# driver_sapog_compact.net
KiCad netlist of a schematic drawn in Altium Designer
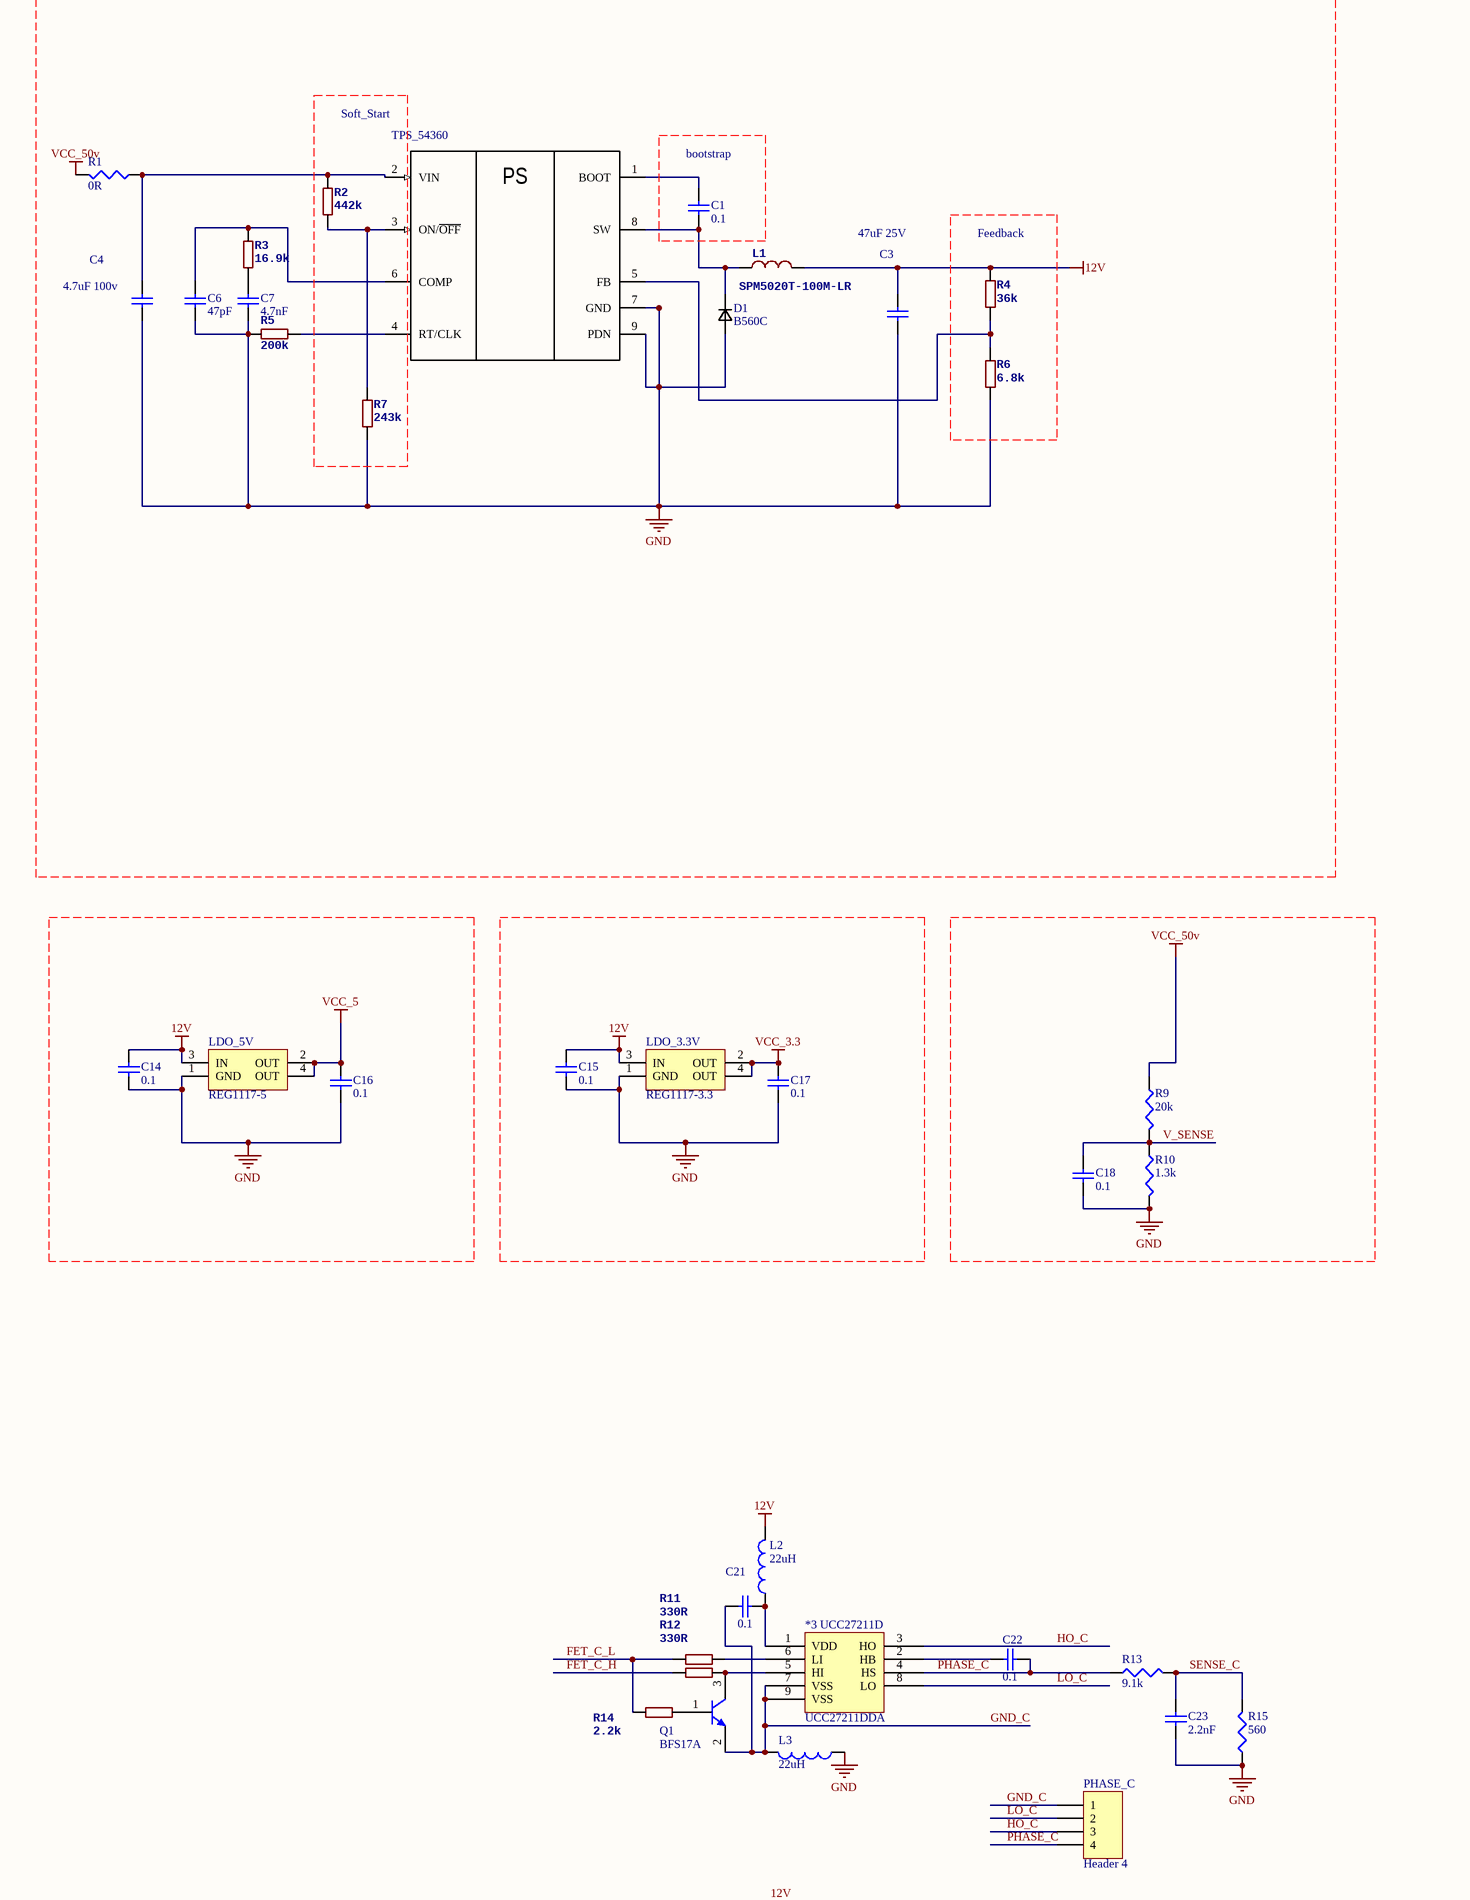
[diagram p0: driver_sapog_compact.SchDoc, top left]
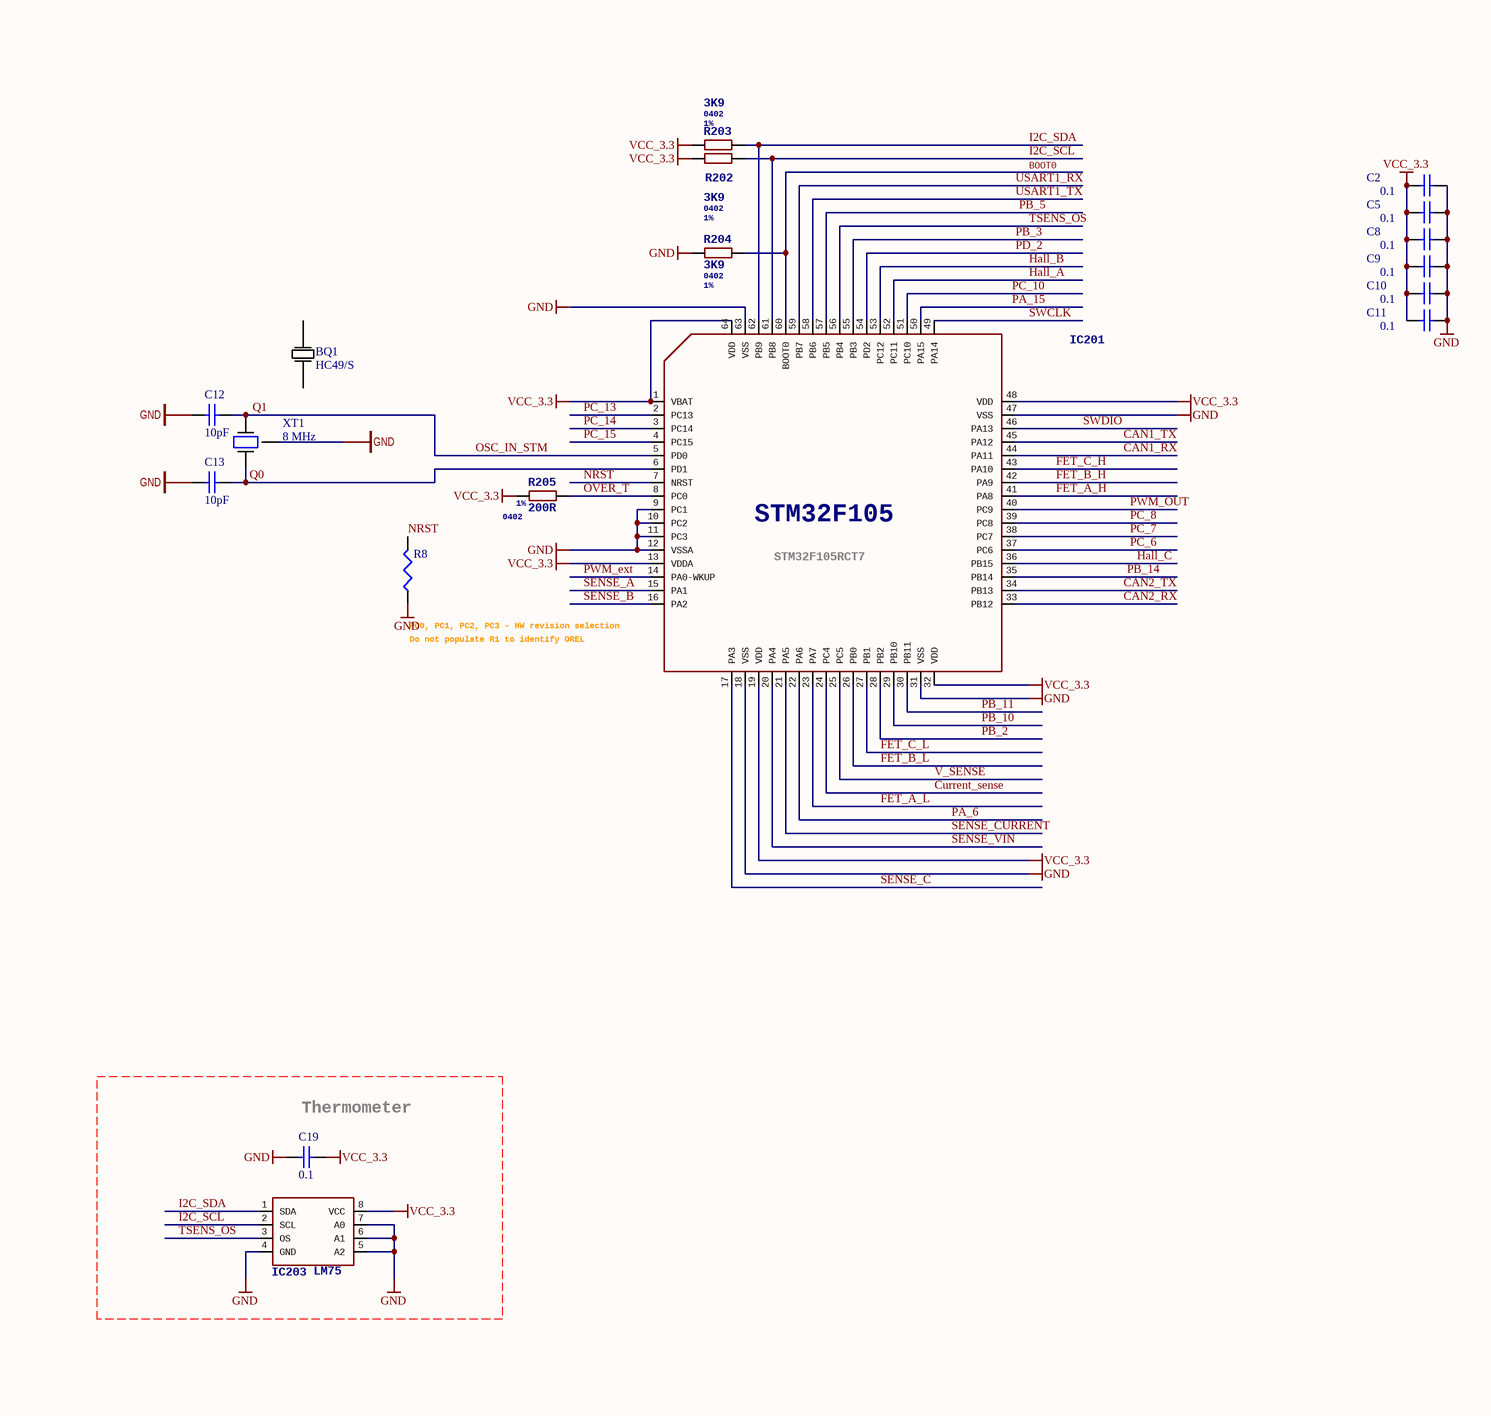
[diagram p1: driver_sapog_compact.SchDoc, top middle]
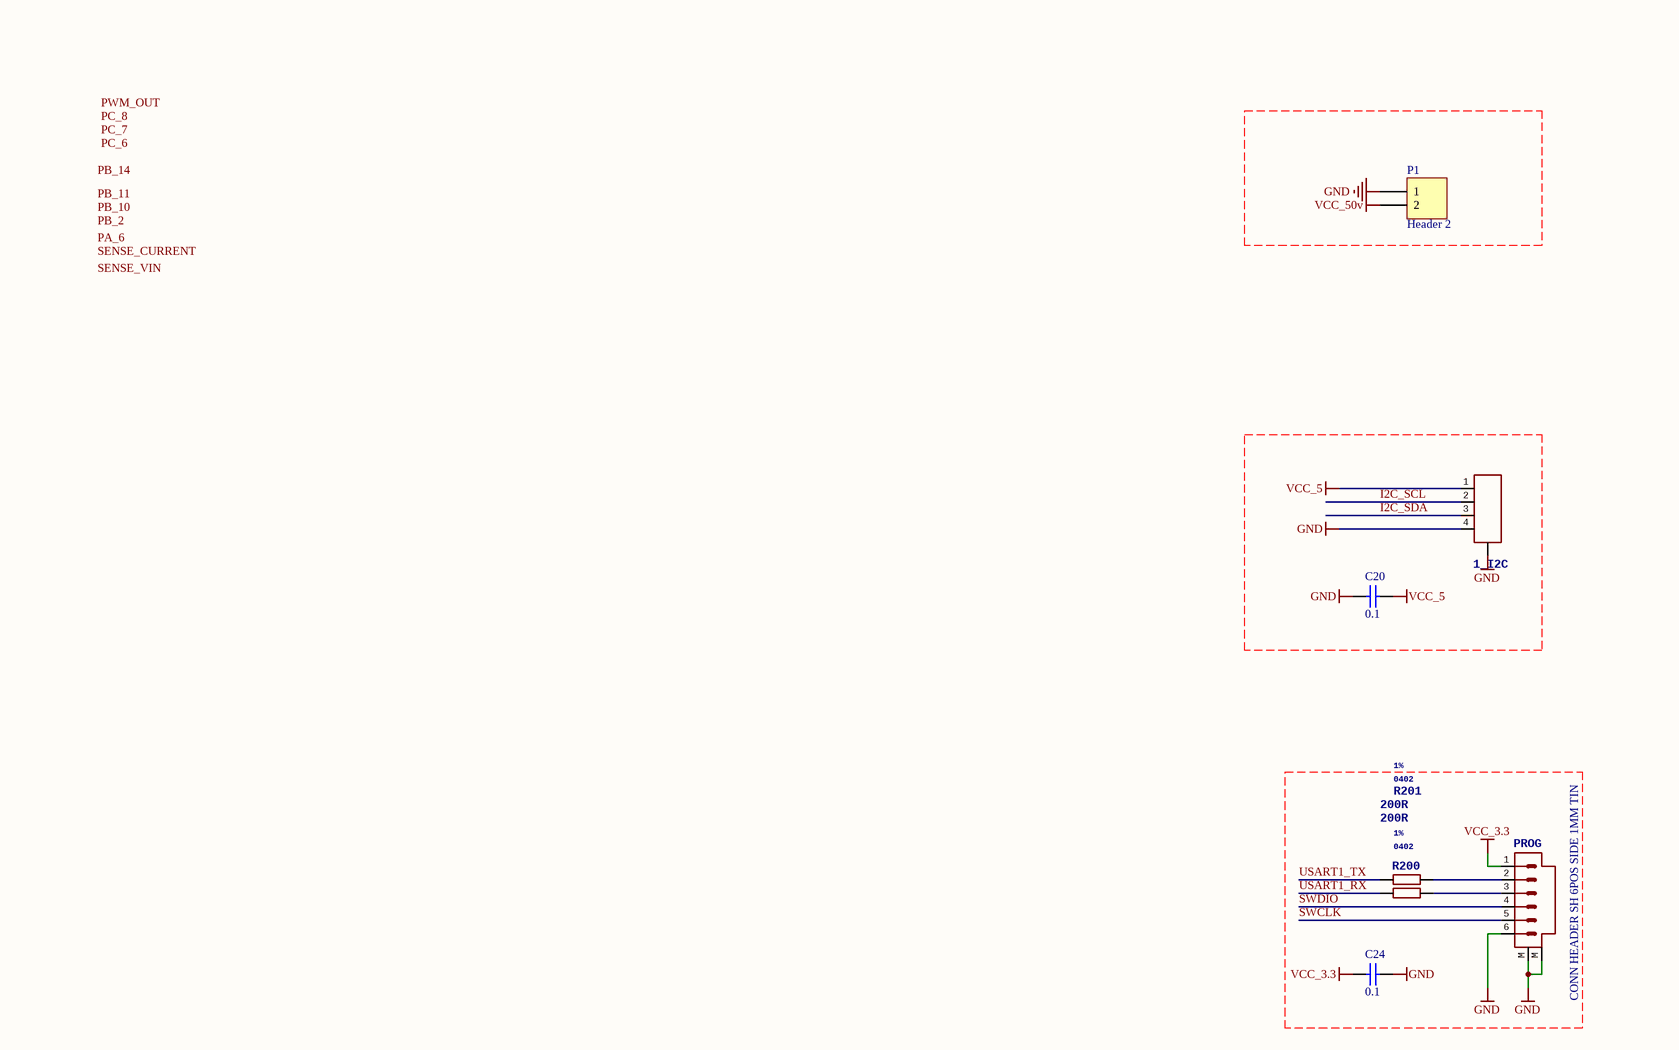
[diagram p2: driver_sapog_compact.SchDoc, top right]
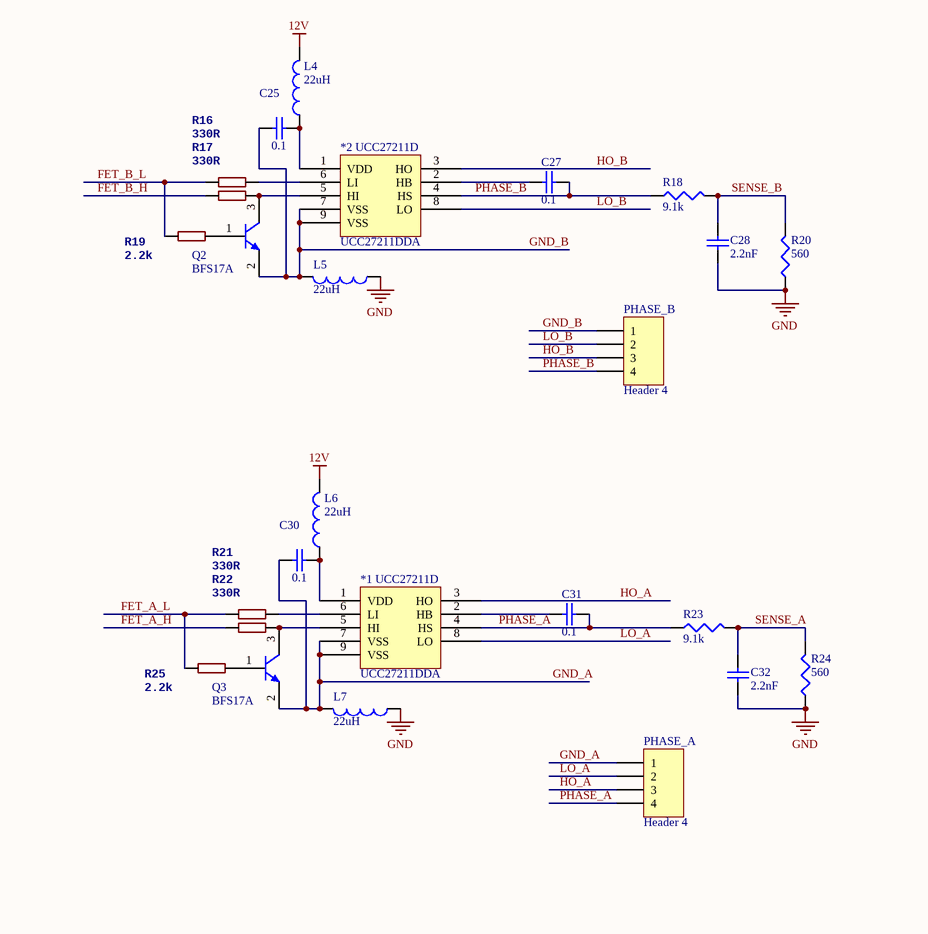
[diagram p3: driver_sapog_compact.SchDoc, bottom left]
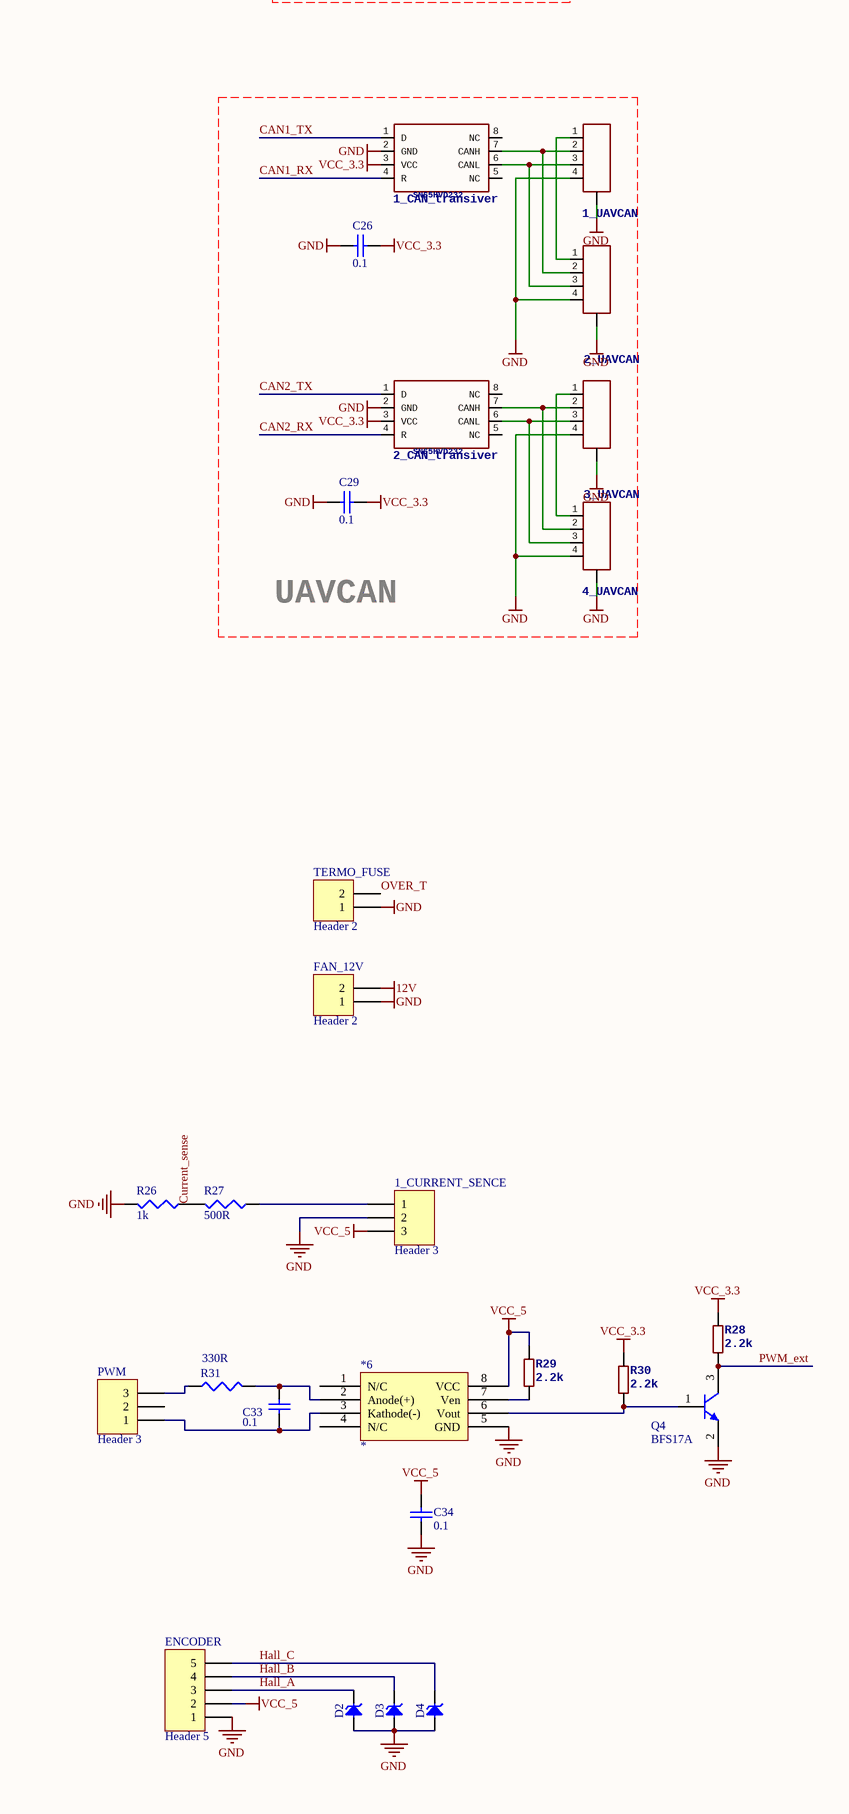
[diagram p4: driver_sapog_compact.SchDoc, bottom right]

(export (version "E")
  (design (tool "Eeschema 10.0.6"))
  (components
    (comp (ref "*1 UCC27211D")
      (value "UCC27211DDA")
      (footprint "Логическая_PLib:D8_L_G")
      (libsource (lib "UCC27211DDA") (part "UCC27211DDA"))
    )
    (comp (ref "*2 UCC27211D")
      (value "UCC27211DDA")
      (footprint "Логическая_PLib:D8_L_G")
      (libsource (lib "UCC27211DDA") (part "UCC27211DDA"))
    )
    (comp (ref "*3 UCC27211D")
      (value "UCC27211DDA")
      (footprint "Логическая_PLib:D8_L_G")
      (libsource (lib "UCC27211DDA") (part "UCC27211DDA"))
    )
    (comp (ref "*6") (value "*") (footprint "UCC37322P") (libsource (lib "HCPL0600") (part "Component_1")))
    (comp (ref "1_CAN_transiver")
      (value "SN65HVD232D")
      (footprint "SOIC8")
      (description "IC CAN TRANSCEIVER 3.3V 8-SOIC")
      (fields (field (name "MANF") "Texas Instruments") (field (name "SN65HVD232") "SN65HVD232"))
      (libsource (lib "sapog_reference_hardware") (part "SN65HVD232D"))
    )
    (comp (ref "1_CURRENT_SENCE")
      (value "Header 3")
      (footprint "HDR1X3")
      (description "Header, 3-Pin")
      (fields (field (name "PUBLISHER") "Altium Limited"))
      (libsource (lib "") (part "Header 3_1"))
    )
    (comp (ref "1_I2C")
      (value "CON-4P-RA")
      (footprint "JST_GH-4P-RA")
      (description "Connector Receptacle 4 Position 0.049\" (1.25mm) Tin Surface Mount, Right Angle")
      (fields (field (name "MANF") "Molex"))
      (libsource (lib "sapog_reference_hardware") (part "CON-4P-RA"))
    )
    (comp (ref "1_UAVCAN")
      (value "CON-4P-RA")
      (footprint "JST_GH-4P-RA")
      (description "Connector Receptacle 4 Position 0.049\" (1.25mm) Tin Surface Mount, Right Angle")
      (fields (field (name "MANF") "Molex"))
      (libsource (lib "sapog_reference_hardware") (part "CON-4P-RA"))
    )
    (comp (ref "2_CAN_transiver")
      (value "SN65HVD232D")
      (footprint "SOIC8")
      (description "IC CAN TRANSCEIVER 3.3V 8-SOIC")
      (fields (field (name "MANF") "Texas Instruments") (field (name "SN65HVD232") "SN65HVD232"))
      (libsource (lib "sapog_reference_hardware") (part "SN65HVD232D"))
    )
    (comp (ref "2_UAVCAN")
      (value "CON-4P-RA")
      (footprint "JST_GH-4P-RA")
      (description "Connector Receptacle 4 Position 0.049\" (1.25mm) Tin Surface Mount, Right Angle")
      (fields (field (name "MANF") "Molex"))
      (libsource (lib "sapog_reference_hardware") (part "CON-4P-RA"))
    )
    (comp (ref "3_UAVCAN")
      (value "CON-4P-RA")
      (footprint "JST_GH-4P-RA")
      (description "Connector Receptacle 4 Position 0.049\" (1.25mm) Tin Surface Mount, Right Angle")
      (fields (field (name "MANF") "Molex"))
      (libsource (lib "sapog_reference_hardware") (part "CON-4P-RA"))
    )
    (comp (ref "4_UAVCAN")
      (value "CON-4P-RA")
      (footprint "JST_GH-4P-RA")
      (description "Connector Receptacle 4 Position 0.049\" (1.25mm) Tin Surface Mount, Right Angle")
      (fields (field (name "MANF") "Molex"))
      (libsource (lib "sapog_reference_hardware") (part "CON-4P-RA"))
    )
    (comp (ref "BQ1")
      (value "HC49/S")
      (footprint "HS49/S")
      (description "Crystal Oscillator")
      (libsource (lib "Логическая_Lib") (part "HC49/S"))
    )
    (comp (ref "C1")
      (value "0.1")
      (footprint "1608[0603]")
      (description "Capacitor (Semiconductor SIM Model)")
      (fields (field (name "PUBLISHER") "Altium Limited"))
      (libsource (lib "Miscellaneous Devices") (part "Cap Semi"))
    )
    (comp (ref "C2")
      (value "0.1")
      (footprint "SMT0603/VISHAY")
      (description "Capacitor (Semiconductor SIM Model)")
      (fields (field (name "PUBLISHER") "Altium Limited"))
      (libsource (lib "Miscellaneous Devices") (part "Cap Semi"))
    )
    (comp (ref "C3")
      (value "47uF 25V")
      (footprint "2220")
      (description "100uF")
      (fields (field (name "Comment") "1206") (field (name "PUBLISHER") "Altium Limited"))
      (libsource (lib "Miscellaneous Devices") (part "Cap Semi"))
    )
    (comp (ref "C4")
      (value "4.7uF 100v")
      (footprint "2220")
      (fields (field (name "Comment") "2220") (field (name "PUBLISHER") "Altium Limited"))
      (libsource (lib "Miscellaneous Devices") (part "Cap Semi"))
    )
    (comp (ref "C5")
      (value "0.1")
      (footprint "SMT0603/VISHAY")
      (description "Capacitor (Semiconductor SIM Model)")
      (fields (field (name "PUBLISHER") "Altium Limited"))
      (libsource (lib "Miscellaneous Devices") (part "Cap Semi"))
    )
    (comp (ref "C6")
      (value "47pF")
      (footprint "SMT0603/VISHAY")
      (description "Capacitor (Semiconductor SIM Model)")
      (fields (field (name "PUBLISHER") "Altium Limited"))
      (libsource (lib "Miscellaneous Devices") (part "Cap Semi"))
    )
    (comp (ref "C7")
      (value "4.7nF")
      (footprint "SMT0603/VISHAY")
      (description "Capacitor (Semiconductor SIM Model)")
      (fields (field (name "PUBLISHER") "Altium Limited"))
      (libsource (lib "Miscellaneous Devices") (part "Cap Semi"))
    )
    (comp (ref "C8")
      (value "0.1")
      (footprint "SMT0603/VISHAY")
      (description "Capacitor (Semiconductor SIM Model)")
      (fields (field (name "PUBLISHER") "Altium Limited"))
      (libsource (lib "Miscellaneous Devices") (part "Cap Semi"))
    )
    (comp (ref "C9")
      (value "0.1")
      (footprint "SMT0603/VISHAY")
      (description "Capacitor (Semiconductor SIM Model)")
      (fields (field (name "PUBLISHER") "Altium Limited"))
      (libsource (lib "Miscellaneous Devices") (part "Cap Semi"))
    )
    (comp (ref "C10")
      (value "0.1")
      (footprint "SMT0603/VISHAY")
      (description "Capacitor (Semiconductor SIM Model)")
      (fields (field (name "PUBLISHER") "Altium Limited"))
      (libsource (lib "Miscellaneous Devices") (part "Cap Semi"))
    )
    (comp (ref "C11")
      (value "0.1")
      (footprint "SMT0603/VISHAY")
      (description "Capacitor (Semiconductor SIM Model)")
      (fields (field (name "PUBLISHER") "Altium Limited"))
      (libsource (lib "Miscellaneous Devices") (part "Cap Semi"))
    )
    (comp (ref "C12")
      (value "10pF")
      (footprint "SMT0603/VISHAY")
      (description "Capacitor (Semiconductor SIM Model)")
      (fields (field (name "PUBLISHER") "Altium Limited"))
      (libsource (lib "Miscellaneous Devices") (part "Cap Semi"))
    )
    (comp (ref "C13")
      (value "10pF")
      (footprint "SMT0603/VISHAY")
      (description "Capacitor (Semiconductor SIM Model)")
      (fields (field (name "PUBLISHER") "Altium Limited"))
      (libsource (lib "Miscellaneous Devices") (part "Cap Semi"))
    )
    (comp (ref "C14")
      (value "0.1")
      (footprint "SMT0603/VISHAY")
      (description "Capacitor (Semiconductor SIM Model)")
      (fields (field (name "PUBLISHER") "Altium Limited"))
      (libsource (lib "Miscellaneous Devices") (part "Cap Semi"))
    )
    (comp (ref "C15")
      (value "0.1")
      (footprint "SMT0603/VISHAY")
      (description "Capacitor (Semiconductor SIM Model)")
      (fields (field (name "PUBLISHER") "Altium Limited"))
      (libsource (lib "Miscellaneous Devices") (part "Cap Semi"))
    )
    (comp (ref "C16")
      (value "0.1")
      (footprint "SMT0603/VISHAY")
      (description "Capacitor (Semiconductor SIM Model)")
      (fields (field (name "PUBLISHER") "Altium Limited"))
      (libsource (lib "Miscellaneous Devices") (part "Cap Semi"))
    )
    (comp (ref "C17")
      (value "0.1")
      (footprint "SMT0603/VISHAY")
      (description "Capacitor (Semiconductor SIM Model)")
      (fields (field (name "PUBLISHER") "Altium Limited"))
      (libsource (lib "Miscellaneous Devices") (part "Cap Semi"))
    )
    (comp (ref "C18")
      (value "0.1")
      (footprint "SMT0603/VISHAY")
      (description "Capacitor (Semiconductor SIM Model)")
      (fields (field (name "PUBLISHER") "Altium Limited"))
      (libsource (lib "Miscellaneous Devices") (part "Cap Semi"))
    )
    (comp (ref "C19")
      (value "0.1")
      (footprint "SMT0603/VISHAY")
      (description "Capacitor (Semiconductor SIM Model)")
      (fields (field (name "PUBLISHER") "Altium Limited"))
      (libsource (lib "Miscellaneous Devices") (part "Cap Semi"))
    )
    (comp (ref "C20")
      (value "0.1")
      (footprint "SMT0603/VISHAY")
      (description "Capacitor (Semiconductor SIM Model)")
      (fields (field (name "PUBLISHER") "Altium Limited"))
      (libsource (lib "Miscellaneous Devices") (part "Cap Semi"))
    )
    (comp (ref "C21")
      (value "0.1")
      (footprint "2220")
      (description "Capacitor (Semiconductor SIM Model)")
      (fields (field (name "PUBLISHER") "Altium Limited"))
      (libsource (lib "Miscellaneous Devices") (part "Cap Semi"))
    )
    (comp (ref "C22")
      (value "0.1")
      (footprint "2220")
      (description "Capacitor (Semiconductor SIM Model)")
      (fields (field (name "PUBLISHER") "Altium Limited"))
      (libsource (lib "Miscellaneous Devices") (part "Cap Semi"))
    )
    (comp (ref "C23")
      (value "2.2nF")
      (footprint "SMT0603/VISHAY")
      (description "Capacitor (Semiconductor SIM Model)")
      (fields (field (name "PUBLISHER") "Altium Limited"))
      (libsource (lib "Miscellaneous Devices") (part "Cap Semi"))
    )
    (comp (ref "C24")
      (value "0.1")
      (footprint "SMT0603/VISHAY")
      (description "Capacitor (Semiconductor SIM Model)")
      (fields (field (name "PUBLISHER") "Altium Limited"))
      (libsource (lib "Miscellaneous Devices") (part "Cap Semi"))
    )
    (comp (ref "C25")
      (value "0.1")
      (footprint "2220")
      (description "Capacitor (Semiconductor SIM Model)")
      (fields (field (name "PUBLISHER") "Altium Limited"))
      (libsource (lib "Miscellaneous Devices") (part "Cap Semi"))
    )
    (comp (ref "C26")
      (value "0.1")
      (footprint "SMT0603/VISHAY")
      (description "Capacitor (Semiconductor SIM Model)")
      (fields (field (name "PUBLISHER") "Altium Limited"))
      (libsource (lib "Miscellaneous Devices") (part "Cap Semi"))
    )
    (comp (ref "C27")
      (value "0.1")
      (footprint "2220")
      (description "Capacitor (Semiconductor SIM Model)")
      (fields (field (name "PUBLISHER") "Altium Limited"))
      (libsource (lib "Miscellaneous Devices") (part "Cap Semi"))
    )
    (comp (ref "C28")
      (value "2.2nF")
      (footprint "SMT0603/VISHAY")
      (description "Capacitor (Semiconductor SIM Model)")
      (fields (field (name "PUBLISHER") "Altium Limited"))
      (libsource (lib "Miscellaneous Devices") (part "Cap Semi"))
    )
    (comp (ref "C29")
      (value "0.1")
      (footprint "SMT0603/VISHAY")
      (description "Capacitor (Semiconductor SIM Model)")
      (fields (field (name "PUBLISHER") "Altium Limited"))
      (libsource (lib "Miscellaneous Devices") (part "Cap Semi"))
    )
    (comp (ref "C30")
      (value "0.1")
      (footprint "2220")
      (description "Capacitor (Semiconductor SIM Model)")
      (fields (field (name "PUBLISHER") "Altium Limited"))
      (libsource (lib "Miscellaneous Devices") (part "Cap Semi"))
    )
    (comp (ref "C31")
      (value "0.1")
      (footprint "2220")
      (description "Capacitor (Semiconductor SIM Model)")
      (fields (field (name "PUBLISHER") "Altium Limited"))
      (libsource (lib "Miscellaneous Devices") (part "Cap Semi"))
    )
    (comp (ref "C32")
      (value "2.2nF")
      (footprint "SMT0603/VISHAY")
      (description "Capacitor (Semiconductor SIM Model)")
      (fields (field (name "PUBLISHER") "Altium Limited"))
      (libsource (lib "Miscellaneous Devices") (part "Cap Semi"))
    )
    (comp (ref "C33")
      (value "0.1")
      (footprint "SMT0603/VISHAY")
      (description "Capacitor (Semiconductor SIM Model)")
      (fields (field (name "PUBLISHER") "Altium Limited"))
      (libsource (lib "Miscellaneous Devices") (part "Cap Semi"))
    )
    (comp (ref "C34")
      (value "0.1")
      (footprint "SMT0603/VISHAY")
      (description "Capacitor (Semiconductor SIM Model)")
      (fields (field (name "PUBLISHER") "Altium Limited"))
      (libsource (lib "Miscellaneous Devices") (part "Cap Semi"))
    )
    (comp (ref "D1")
      (value "B560C")
      (footprint "SMC")
      (description "60V 0.5A Shottcky Diode")
      (libsource (lib "Логическая_Lib") (part "B560C"))
    )
    (comp (ref "D2")
      (value "BZV55-B13")
      (footprint "3.2x1.6x1.1")
      (description "Zener Diode")
      (fields
        (field (name "VOLTAGE") "13V")
        (field (name "POWER") "500mW")
        (field (name "AUTHOR") "CERN DEM JLC")
      )
      (libsource (lib "ICs And Semiconductors") (part "Diode Zener"))
    )
    (comp (ref "D3")
      (value "BZV55-B13")
      (footprint "3.2x1.6x1.1")
      (description "Zener Diode")
      (fields
        (field (name "VOLTAGE") "13V")
        (field (name "POWER") "500mW")
        (field (name "AUTHOR") "CERN DEM JLC")
      )
      (libsource (lib "ICs And Semiconductors") (part "Diode Zener"))
    )
    (comp (ref "D4")
      (value "BZV55-B13")
      (footprint "3.2x1.6x1.1")
      (description "Zener Diode")
      (fields
        (field (name "VOLTAGE") "13V")
        (field (name "POWER") "500mW")
        (field (name "AUTHOR") "CERN DEM JLC")
      )
      (libsource (lib "ICs And Semiconductors") (part "Diode Zener"))
    )
    (comp (ref "ENCODER")
      (value "Header 5")
      (footprint "jst_gh_6_pin")
      (description "Header, 5-Pin")
      (fields (field (name "PUBLISHER") "Altium Limited"))
      (libsource (lib "Miscellaneous Connectors") (part "Header 5"))
    )
    (comp (ref "FAN_12V")
      (value "Header 2")
      (footprint "HDR1X2")
      (description "Header, 2-Pin")
      (fields (field (name "PUBLISHER") "Altium Limited"))
      (libsource (lib "Miscellaneous Connectors") (part "Header 2"))
    )
    (comp (ref "IC201")
      (value "STM32F105")
      (footprint "sapog_reference_hardware:TQFP64-10X10")
      (description "MCU ARM 256KB FLASH MEM 64-LQFP")
      (fields (field (name "MANF") "STMicroelectronics") (field (name "STM32F105") "STM32F105"))
      (libsource (lib "sapog_reference_hardware") (part "STM32F105"))
    )
    (comp (ref "IC203")
      (value "LM75BD-TSSOP8")
      (footprint "TSSOP8")
      (description "SENSOR TEMPERATURE I2C 8TSSOP")
      (fields (field (name "MANF") "NXP Semiconductors") (field (name "LM75") "LM75"))
      (libsource (lib "sapog_reference_hardware") (part "LM75BD-TSSOP8"))
    )
    (comp (ref "L1")
      (value "SPM5020T-100M-LR")
      (footprint "RBQ:Inductor")
      (libsource (lib "sapog_reference_hardware") (part "L-EPCOS_B82464"))
    )
    (comp (ref "L2")
      (value "22uH")
      (footprint "0805")
      (description "0805")
      (fields (field (name "PUBLISHER") "Altium Limited"))
      (libsource (lib "Miscellaneous Devices") (part "Inductor"))
    )
    (comp (ref "L3")
      (value "22uH")
      (footprint "0805")
      (description "0805")
      (fields (field (name "PUBLISHER") "Altium Limited"))
      (libsource (lib "Miscellaneous Devices") (part "Inductor"))
    )
    (comp (ref "L4")
      (value "22uH")
      (footprint "0805")
      (description "0805")
      (fields (field (name "PUBLISHER") "Altium Limited"))
      (libsource (lib "Miscellaneous Devices") (part "Inductor"))
    )
    (comp (ref "L5")
      (value "22uH")
      (footprint "0805")
      (description "0805")
      (fields (field (name "PUBLISHER") "Altium Limited"))
      (libsource (lib "Miscellaneous Devices") (part "Inductor"))
    )
    (comp (ref "L6")
      (value "22uH")
      (footprint "0805")
      (description "0805")
      (fields (field (name "PUBLISHER") "Altium Limited"))
      (libsource (lib "Miscellaneous Devices") (part "Inductor"))
    )
    (comp (ref "L7")
      (value "22uH")
      (footprint "0805")
      (description "0805")
      (fields (field (name "PUBLISHER") "Altium Limited"))
      (libsource (lib "Miscellaneous Devices") (part "Inductor"))
    )
    (comp (ref "LDO_3.3V")
      (value "REG1117-3.3")
      (footprint "ZZ311")
      (description "800mA and 1A Low Dropout Positive Regulator 2.85V, 3.3V, 5V, and Adjustable")
      (fields (field (name "PUBLISHER") "Altium Limited"))
      (libsource (lib "BB Power Mgt Voltage Regulator") (part "REG1117-5"))
    )
    (comp (ref "LDO_5V")
      (value "REG1117-5")
      (footprint "ZZ311")
      (description "800mA and 1A Low Dropout Positive Regulator 2.85V, 3.3V, 5V, and Adjustable")
      (fields (field (name "PUBLISHER") "Altium Limited"))
      (libsource (lib "BB Power Mgt Voltage Regulator") (part "REG1117-5"))
    )
    (comp (ref "P1")
      (value "Header 2")
      (footprint "HDR1X2")
      (description "Header, 2-Pin")
      (fields (field (name "PUBLISHER") "Altium Limited"))
      (libsource (lib "") (part "Header 2_1"))
    )
    (comp (ref "PHASE_A")
      (value "Header 4")
      (footprint "HDR1X4")
      (description "Header, 4-Pin")
      (fields (field (name "PUBLISHER") "Altium Limited"))
      (libsource (lib "Miscellaneous Connectors") (part "Header 4"))
    )
    (comp (ref "PHASE_B")
      (value "Header 4")
      (footprint "HDR1X4")
      (description "Header, 4-Pin")
      (fields (field (name "PUBLISHER") "Altium Limited"))
      (libsource (lib "Miscellaneous Connectors") (part "Header 4"))
    )
    (comp (ref "PHASE_C")
      (value "Header 4")
      (footprint "HDR1X4")
      (description "Header, 4-Pin")
      (fields (field (name "PUBLISHER") "Altium Limited"))
      (libsource (lib "Miscellaneous Connectors") (part "Header 4"))
    )
    (comp (ref "PROG")
      (value "CONN HEADER SH 6POS SIDE 1MM TIN")
      (footprint "HIROSE DF13-6P-1.25H")
      (fields (field (name "MANF") "JST Sales America Inc"))
      (libsource (lib "sapog_reference_hardware") (part "DF13_6P_1"))
    )
    (comp (ref "PWM")
      (value "Header 3")
      (footprint "HDR1X3")
      (description "Header, 3-Pin")
      (fields (field (name "PUBLISHER") "Altium Limited"))
      (libsource (lib "Miscellaneous Connectors") (part "Header 3"))
    )
    (comp (ref "Q1")
      (value "BFS17A")
      (footprint "SOT-23_N")
      (description "NPN General Purpose Amplifier")
      (fields (field (name "PUBLISHER") "Altium Limited"))
      (libsource (lib "Miscellaneous Devices") (part "2N3904"))
    )
    (comp (ref "Q2")
      (value "BFS17A")
      (footprint "SOT-23_N")
      (description "NPN General Purpose Amplifier")
      (fields (field (name "PUBLISHER") "Altium Limited"))
      (libsource (lib "Miscellaneous Devices") (part "2N3904"))
    )
    (comp (ref "Q3")
      (value "BFS17A")
      (footprint "SOT-23_N")
      (description "NPN General Purpose Amplifier")
      (fields (field (name "PUBLISHER") "Altium Limited"))
      (libsource (lib "Miscellaneous Devices") (part "2N3904"))
    )
    (comp (ref "Q4")
      (value "BFS17A")
      (footprint "SOT-23_N")
      (description "NPN General Purpose Amplifier")
      (fields (field (name "PUBLISHER") "Altium Limited"))
      (libsource (lib "Miscellaneous Devices") (part "2N3904"))
    )
    (comp (ref "R1")
      (value "0R")
      (footprint "14-1210")
      (description "fuse")
      (fields (field (name "Comment") "1210") (field (name "PUBLISHER") "Altium Limited"))
      (libsource (lib "Miscellaneous Devices") (part "Res3"))
    )
    (comp (ref "R2")
      (value "442k")
      (footprint "SMT0603/VISHAY")
      (libsource (lib "sapog_reference_hardware") (part "R0402"))
    )
    (comp (ref "R3")
      (value "16.9k")
      (footprint "SMT0603/VISHAY")
      (libsource (lib "sapog_reference_hardware") (part "R0402"))
    )
    (comp (ref "R4")
      (value "36k")
      (footprint "SMT0603/VISHAY")
      (libsource (lib "sapog_reference_hardware") (part "R0402"))
    )
    (comp (ref "R5")
      (value "200k")
      (footprint "SMT0603/VISHAY")
      (libsource (lib "sapog_reference_hardware") (part "R0402"))
    )
    (comp (ref "R6")
      (value "6.8k")
      (footprint "SMT0603/VISHAY")
      (libsource (lib "sapog_reference_hardware") (part "R0402"))
    )
    (comp (ref "R7")
      (value "243k")
      (footprint "SMT0603/VISHAY")
      (libsource (lib "sapog_reference_hardware") (part "R0402"))
    )
    (comp (ref "R8")
      (value "Res3")
      (footprint "SMT0603/VISHAY")
      (description "Resistor")
      (fields (field (name "PUBLISHER") "Altium Limited"))
      (libsource (lib "Miscellaneous Devices") (part "Res3"))
    )
    (comp (ref "R9")
      (value "20k")
      (footprint "SMT0603/VISHAY")
      (description "Resistor")
      (fields (field (name "Comment") "10k") (field (name "PUBLISHER") "Altium Limited"))
      (libsource (lib "Miscellaneous Devices") (part "Res3"))
    )
    (comp (ref "R10")
      (value "1.3k")
      (footprint "SMT0603/VISHAY")
      (description "Resistor")
      (fields (field (name "Comment") "1k") (field (name "PUBLISHER") "Altium Limited"))
      (libsource (lib "Miscellaneous Devices") (part "Res3"))
    )
    (comp (ref "R11")
      (value "330R")
      (footprint "1608[0603]")
      (libsource (lib "sapog_reference_hardware") (part "R0402"))
    )
    (comp (ref "R12")
      (value "330R")
      (footprint "1608[0603]")
      (libsource (lib "sapog_reference_hardware") (part "R0402"))
    )
    (comp (ref "R13")
      (value "9.1k")
      (footprint "SMT0603/VISHAY")
      (description "Resistor")
      (fields (field (name "PUBLISHER") "Altium Limited"))
      (libsource (lib "Miscellaneous Devices") (part "Res3"))
    )
    (comp (ref "R14")
      (value "2.2k")
      (footprint "1608[0603]")
      (libsource (lib "sapog_reference_hardware") (part "R0402"))
    )
    (comp (ref "R15")
      (value "560")
      (footprint "SMT0603/VISHAY")
      (description "Resistor")
      (fields (field (name "Comment") "560R") (field (name "PUBLISHER") "Altium Limited"))
      (libsource (lib "Miscellaneous Devices") (part "Res3"))
    )
    (comp (ref "R16")
      (value "330R")
      (footprint "1608[0603]")
      (libsource (lib "sapog_reference_hardware") (part "R0402"))
    )
    (comp (ref "R17")
      (value "330R")
      (footprint "1608[0603]")
      (libsource (lib "sapog_reference_hardware") (part "R0402"))
    )
    (comp (ref "R18")
      (value "9.1k")
      (footprint "SMT0603/VISHAY")
      (description "Resistor")
      (fields (field (name "PUBLISHER") "Altium Limited"))
      (libsource (lib "Miscellaneous Devices") (part "Res3"))
    )
    (comp (ref "R19")
      (value "2.2k")
      (footprint "1608[0603]")
      (libsource (lib "sapog_reference_hardware") (part "R0402"))
    )
    (comp (ref "R20")
      (value "560")
      (footprint "SMT0603/VISHAY")
      (description "Resistor")
      (fields (field (name "Comment") "560R") (field (name "PUBLISHER") "Altium Limited"))
      (libsource (lib "Miscellaneous Devices") (part "Res3"))
    )
    (comp (ref "R21")
      (value "330R")
      (footprint "1608[0603]")
      (libsource (lib "sapog_reference_hardware") (part "R0402"))
    )
    (comp (ref "R22")
      (value "330R")
      (footprint "1608[0603]")
      (libsource (lib "sapog_reference_hardware") (part "R0402"))
    )
    (comp (ref "R23")
      (value "9.1k")
      (footprint "SMT0603/VISHAY")
      (description "Resistor")
      (fields (field (name "PUBLISHER") "Altium Limited"))
      (libsource (lib "Miscellaneous Devices") (part "Res3"))
    )
    (comp (ref "R24")
      (value "560")
      (footprint "SMT0603/VISHAY")
      (description "Resistor")
      (fields (field (name "Comment") "560R") (field (name "PUBLISHER") "Altium Limited"))
      (libsource (lib "Miscellaneous Devices") (part "Res3"))
    )
    (comp (ref "R25")
      (value "2.2k")
      (footprint "1608[0603]")
      (libsource (lib "sapog_reference_hardware") (part "R0402"))
    )
    (comp (ref "R26")
      (value "1k")
      (footprint "SMT0603/VISHAY")
      (description "Resistor")
      (fields (field (name "PUBLISHER") "Altium Limited"))
      (libsource (lib "Miscellaneous Devices") (part "Res3"))
    )
    (comp (ref "R27")
      (value "500R")
      (footprint "SMT0603/VISHAY")
      (description "Resistor")
      (fields (field (name "Comment") "560R") (field (name "PUBLISHER") "Altium Limited"))
      (libsource (lib "Miscellaneous Devices") (part "Res3"))
    )
    (comp (ref "R28")
      (value "2.2k")
      (footprint "1608[0603]")
      (libsource (lib "sapog_reference_hardware") (part "R0402"))
    )
    (comp (ref "R29")
      (value "2.2k")
      (footprint "1608[0603]")
      (libsource (lib "sapog_reference_hardware") (part "R0402"))
    )
    (comp (ref "R30")
      (value "2.2k")
      (footprint "1608[0603]")
      (libsource (lib "sapog_reference_hardware") (part "R0402"))
    )
    (comp (ref "R31")
      (value "330R")
      (footprint "SMT0603/VISHAY")
      (description "Resistor")
      (fields (field (name "PUBLISHER") "Altium Limited"))
      (libsource (lib "Miscellaneous Devices") (part "Res3"))
    )
    (comp (ref "R200")
      (value "200R")
      (footprint "SMT0603/VISHAY")
      (fields
        (field (name "MANF") "Yageo")
        (field (name "PARTNO") "RC0402FR-07240RL")
        (field (name "PACKAGE") "0402")
        (field (name "TOLERANCE") "1%")
      )
      (libsource (lib "R_digikey") (part "200R-0402"))
    )
    (comp (ref "R201")
      (value "200R")
      (footprint "SMT0603/VISHAY")
      (fields
        (field (name "MANF") "Yageo")
        (field (name "PARTNO") "RC0402FR-07240RL")
        (field (name "PACKAGE") "0402")
        (field (name "TOLERANCE") "1%")
      )
      (libsource (lib "R_digikey") (part "200R-0402"))
    )
    (comp (ref "R202")
      (value "3K9")
      (footprint "SMT0603/VISHAY")
      (fields (field (name "MANF") "Yageo") (field (name "PACKAGE") "0402") (field (name "TOLERANCE") "1%"))
      (libsource (lib "R_digikey") (part "3K9-0402"))
    )
    (comp (ref "R203")
      (value "3K9")
      (footprint "SMT0603/VISHAY")
      (fields (field (name "MANF") "Yageo") (field (name "PACKAGE") "0402") (field (name "TOLERANCE") "1%"))
      (libsource (lib "R_digikey") (part "3K9-0402"))
    )
    (comp (ref "R204")
      (value "3K9")
      (footprint "SMT0603/VISHAY")
      (fields (field (name "MANF") "Yageo") (field (name "PACKAGE") "0402") (field (name "TOLERANCE") "1%"))
      (libsource (lib "R_digikey") (part "3K9-0402"))
    )
    (comp (ref "R205")
      (value "200R")
      (footprint "SMT0603/VISHAY")
      (fields (field (name "MANF") "Yageo") (field (name "PACKAGE") "0402") (field (name "TOLERANCE") "1%"))
      (libsource (lib "R_digikey") (part "200R-0402"))
    )
    (comp (ref "TERMO_FUSE")
      (value "Header 2")
      (footprint "HDR1X2")
      (description "Header, 2-Pin")
      (fields (field (name "PUBLISHER") "Altium Limited"))
      (libsource (lib "Miscellaneous Connectors") (part "Header 2"))
    )
    (comp (ref "TPS_54360")
      (value "~")
      (footprint "Логическая_PLib:D8_L_G")
      (description "150mA Low-Noise Low-Dropout Regulator Whit Shutdown")
      (libsource (lib "Логическая_Lib") (part "TPS54560"))
    )
    (comp (ref "XT1")
      (value "8 MHz")
      (footprint "DFN220P320X110-4N")
      (description "FA-238 16.0000MB-C3")
      (fields
        (field (name "MANUFACTURER") "Abracon LLC")
        (field (name "MANUFACTURER PART NUMBER") "ABM3B-8.000MHZ-10-1-U-T")
      )
      (libsource (lib "CustomComponents") (part "ABM3B-8.000MHZ-10-1-U-T"))
    )
  )
  (nets
    (net (code "1") (name "/BOOT0") (class "Default")
      (node (ref "IC201") (pin "60") (pinfunction "BOOT0_60") (pintype "passive"))
      (node (ref "R204") (pin "2") (pinfunction "2_2") (pintype "passive"))
    )
    (net (code "2") (name "/CAN1_RX") (class "Default")
      (node (ref "1_CAN_transiver") (pin "4") (pinfunction "R_4") (pintype "passive"))
      (node (ref "IC201") (pin "44") (pinfunction "PA11_44") (pintype "passive"))
    )
    (net (code "3") (name "/CAN1_TX") (class "Default")
      (node (ref "1_CAN_transiver") (pin "1") (pinfunction "D_1") (pintype "passive"))
      (node (ref "IC201") (pin "45") (pinfunction "PA12_45") (pintype "passive"))
    )
    (net (code "4") (name "/CAN2_RX") (class "Default")
      (node (ref "2_CAN_transiver") (pin "4") (pinfunction "R_4") (pintype "passive"))
      (node (ref "IC201") (pin "33") (pinfunction "PB12_33") (pintype "passive"))
    )
    (net (code "5") (name "/CAN2_TX") (class "Default")
      (node (ref "2_CAN_transiver") (pin "1") (pinfunction "D_1") (pintype "passive"))
      (node (ref "IC201") (pin "34") (pinfunction "PB13_34") (pintype "passive"))
    )
    (net (code "6") (name "/Current_sense") (class "Default")
      (node (ref "IC201") (pin "24") (pinfunction "PC4_24") (pintype "passive"))
      (node (ref "R26") (pin "1") (pinfunction "1_1") (pintype "passive"))
      (node (ref "R27") (pin "2") (pinfunction "2_2") (pintype "passive"))
    )
    (net (code "7") (name "/FET_A_H") (class "Default")
      (node (ref "IC201") (pin "41") (pinfunction "PA8_41") (pintype "passive"))
      (node (ref "R21") (pin "2") (pinfunction "2_2") (pintype "passive"))
    )
    (net (code "8") (name "/FET_A_L") (class "Default")
      (node (ref "IC201") (pin "23") (pinfunction "PA7_23") (pintype "passive"))
      (node (ref "R22") (pin "2") (pinfunction "2_2") (pintype "passive"))
      (node (ref "R25") (pin "2") (pinfunction "2_2") (pintype "passive"))
    )
    (net (code "9") (name "/FET_B_H") (class "Default")
      (node (ref "IC201") (pin "42") (pinfunction "PA9_42") (pintype "passive"))
      (node (ref "R16") (pin "2") (pinfunction "2_2") (pintype "passive"))
    )
    (net (code "10") (name "/FET_B_L") (class "Default")
      (node (ref "IC201") (pin "26") (pinfunction "PB0_26") (pintype "passive"))
      (node (ref "R17") (pin "2") (pinfunction "2_2") (pintype "passive"))
      (node (ref "R19") (pin "2") (pinfunction "2_2") (pintype "passive"))
    )
    (net (code "11") (name "/FET_C_H") (class "Default")
      (node (ref "IC201") (pin "43") (pinfunction "PA10_43") (pintype "passive"))
      (node (ref "R11") (pin "2") (pinfunction "2_2") (pintype "passive"))
    )
    (net (code "12") (name "/FET_C_L") (class "Default")
      (node (ref "IC201") (pin "27") (pinfunction "PB1_27") (pintype "passive"))
      (node (ref "R12") (pin "2") (pinfunction "2_2") (pintype "passive"))
      (node (ref "R14") (pin "2") (pinfunction "2_2") (pintype "passive"))
    )
    (net (code "13") (name "/GND_A") (class "Default")
      (node (ref "*1 UCC27211D") (pin "7") (pinfunction "VSS_7") (pintype "passive"))
      (node (ref "*1 UCC27211D") (pin "9") (pinfunction "VSS_9") (pintype "passive"))
      (node (ref "C30") (pin "2") (pinfunction "2_2") (pintype "passive"))
      (node (ref "L7") (pin "2") (pinfunction "2_2") (pintype "passive"))
      (node (ref "PHASE_A") (pin "1") (pinfunction "1_1") (pintype "passive"))
      (node (ref "Q3") (pin "2") (pinfunction "E_2") (pintype "passive"))
    )
    (net (code "14") (name "/GND_B") (class "Default")
      (node (ref "*2 UCC27211D") (pin "7") (pinfunction "VSS_7") (pintype "passive"))
      (node (ref "*2 UCC27211D") (pin "9") (pinfunction "VSS_9") (pintype "passive"))
      (node (ref "C25") (pin "2") (pinfunction "2_2") (pintype "passive"))
      (node (ref "L5") (pin "2") (pinfunction "2_2") (pintype "passive"))
      (node (ref "PHASE_B") (pin "1") (pinfunction "1_1") (pintype "passive"))
      (node (ref "Q2") (pin "2") (pinfunction "E_2") (pintype "passive"))
    )
    (net (code "15") (name "/GND_C") (class "Default")
      (node (ref "*3 UCC27211D") (pin "7") (pinfunction "VSS_7") (pintype "passive"))
      (node (ref "*3 UCC27211D") (pin "9") (pinfunction "VSS_9") (pintype "passive"))
      (node (ref "C21") (pin "2") (pinfunction "2_2") (pintype "passive"))
      (node (ref "L3") (pin "2") (pinfunction "2_2") (pintype "passive"))
      (node (ref "PHASE_C") (pin "1") (pinfunction "1_1") (pintype "passive"))
      (node (ref "Q1") (pin "2") (pinfunction "E_2") (pintype "passive"))
    )
    (net (code "16") (name "/HO_A") (class "Default")
      (node (ref "*1 UCC27211D") (pin "3") (pinfunction "HO_3") (pintype "passive"))
      (node (ref "PHASE_A") (pin "3") (pinfunction "3_3") (pintype "passive"))
    )
    (net (code "17") (name "/HO_B") (class "Default")
      (node (ref "*2 UCC27211D") (pin "3") (pinfunction "HO_3") (pintype "passive"))
      (node (ref "PHASE_B") (pin "3") (pinfunction "3_3") (pintype "passive"))
    )
    (net (code "18") (name "/HO_C") (class "Default")
      (node (ref "*3 UCC27211D") (pin "3") (pinfunction "HO_3") (pintype "passive"))
      (node (ref "PHASE_C") (pin "3") (pinfunction "3_3") (pintype "passive"))
    )
    (net (code "19") (name "/Hall_A") (class "Default")
      (node (ref "D2") (pin "1") (pinfunction "C_1") (pintype "passive"))
      (node (ref "ENCODER") (pin "3") (pinfunction "3_3") (pintype "passive"))
      (node (ref "IC201") (pin "52") (pinfunction "PC11_52") (pintype "passive"))
    )
    (net (code "20") (name "/Hall_B") (class "Default")
      (node (ref "D3") (pin "1") (pinfunction "C_1") (pintype "passive"))
      (node (ref "ENCODER") (pin "4") (pinfunction "4_4") (pintype "passive"))
      (node (ref "IC201") (pin "53") (pinfunction "PC12_53") (pintype "passive"))
    )
    (net (code "21") (name "/Hall_C") (class "Default")
      (node (ref "D4") (pin "1") (pinfunction "C_1") (pintype "passive"))
      (node (ref "ENCODER") (pin "5") (pinfunction "5_5") (pintype "passive"))
      (node (ref "IC201") (pin "36") (pinfunction "PB15_36") (pintype "passive"))
    )
    (net (code "22") (name "/I2C_SCL") (class "Default")
      (node (ref "1_I2C") (pin "2") (pinfunction "2_2") (pintype "passive"))
      (node (ref "IC201") (pin "61") (pinfunction "PB8_61") (pintype "passive"))
      (node (ref "IC203") (pin "2") (pinfunction "SCL_2") (pintype "passive"))
      (node (ref "R202") (pin "2") (pinfunction "2_2") (pintype "passive"))
    )
    (net (code "23") (name "/I2C_SDA") (class "Default")
      (node (ref "1_I2C") (pin "3") (pinfunction "3_3") (pintype "passive"))
      (node (ref "IC201") (pin "62") (pinfunction "PB9_62") (pintype "passive"))
      (node (ref "IC203") (pin "1") (pinfunction "SDA_1") (pintype "passive"))
      (node (ref "R203") (pin "2") (pinfunction "2_2") (pintype "passive"))
    )
    (net (code "24") (name "/LO_A") (class "Default")
      (node (ref "*1 UCC27211D") (pin "8") (pinfunction "LO_8") (pintype "passive"))
      (node (ref "PHASE_A") (pin "2") (pinfunction "2_2") (pintype "passive"))
    )
    (net (code "25") (name "/LO_B") (class "Default")
      (node (ref "*2 UCC27211D") (pin "8") (pinfunction "LO_8") (pintype "passive"))
      (node (ref "PHASE_B") (pin "2") (pinfunction "2_2") (pintype "passive"))
    )
    (net (code "26") (name "/LO_C") (class "Default")
      (node (ref "*3 UCC27211D") (pin "8") (pinfunction "LO_8") (pintype "passive"))
      (node (ref "PHASE_C") (pin "2") (pinfunction "2_2") (pintype "passive"))
    )
    (net (code "27") (name "/NRST") (class "Default")
      (node (ref "IC201") (pin "7") (pinfunction "NRST_7") (pintype "passive"))
      (node (ref "R8") (pin "2") (pinfunction "2_2") (pintype "passive"))
    )
    (net (code "28") (name "/OSC_IN_STM") (class "Default")
      (node (ref "C12") (pin "2") (pinfunction "2_2") (pintype "passive"))
      (node (ref "IC201") (pin "5") (pinfunction "PD0_5") (pintype "passive"))
      (node (ref "XT1") (pin "3") (pintype "passive"))
    )
    (net (code "29") (name "/OVER_T") (class "Default")
      (node (ref "IC201") (pin "8") (pinfunction "PC0_8") (pintype "passive"))
      (node (ref "R205") (pin "1") (pinfunction "1_1") (pintype "passive"))
      (node (ref "TERMO_FUSE") (pin "2") (pinfunction "2_2") (pintype "passive"))
    )
    (net (code "30") (name "/PA_6") (class "Default")
      (node (ref "IC201") (pin "22") (pinfunction "PA6_22") (pintype "passive"))
    )
    (net (code "31") (name "/PA_15") (class "Default")
      (node (ref "IC201") (pin "50") (pinfunction "PA15_50") (pintype "passive"))
    )
    (net (code "32") (name "/PB_2") (class "Default")
      (node (ref "IC201") (pin "28") (pinfunction "PB2_28") (pintype "passive"))
    )
    (net (code "33") (name "/PB_3") (class "Default")
      (node (ref "IC201") (pin "55") (pinfunction "PB3_55") (pintype "passive"))
    )
    (net (code "34") (name "/PB_5") (class "Default")
      (node (ref "IC201") (pin "57") (pinfunction "PB5_57") (pintype "passive"))
    )
    (net (code "35") (name "/PB_10") (class "Default")
      (node (ref "IC201") (pin "29") (pinfunction "PB10_29") (pintype "passive"))
    )
    (net (code "36") (name "/PB_11") (class "Default")
      (node (ref "IC201") (pin "30") (pinfunction "PB11_30") (pintype "passive"))
    )
    (net (code "37") (name "/PB_14") (class "Default")
      (node (ref "IC201") (pin "35") (pinfunction "PB14_35") (pintype "passive"))
    )
    (net (code "38") (name "/PC_6") (class "Default")
      (node (ref "IC201") (pin "37") (pinfunction "PC6_37") (pintype "passive"))
    )
    (net (code "39") (name "/PC_7") (class "Default")
      (node (ref "IC201") (pin "38") (pinfunction "PC7_38") (pintype "passive"))
    )
    (net (code "40") (name "/PC_8") (class "Default")
      (node (ref "IC201") (pin "39") (pinfunction "PC8_39") (pintype "passive"))
    )
    (net (code "41") (name "/PC_10") (class "Default")
      (node (ref "IC201") (pin "51") (pinfunction "PC10_51") (pintype "passive"))
    )
    (net (code "42") (name "/PC_13") (class "Default")
      (node (ref "IC201") (pin "2") (pinfunction "PC13_2") (pintype "passive"))
    )
    (net (code "43") (name "/PC_14") (class "Default")
      (node (ref "IC201") (pin "3") (pinfunction "PC14_3") (pintype "passive"))
    )
    (net (code "44") (name "/PC_15") (class "Default")
      (node (ref "IC201") (pin "4") (pinfunction "PC15_4") (pintype "passive"))
    )
    (net (code "45") (name "/PD_2") (class "Default")
      (node (ref "IC201") (pin "54") (pinfunction "PD2_54") (pintype "passive"))
    )
    (net (code "46") (name "/PHASE_A") (class "Default")
      (node (ref "*1 UCC27211D") (pin "4") (pinfunction "HS_4") (pintype "passive"))
      (node (ref "C31") (pin "2") (pinfunction "2_2") (pintype "passive"))
      (node (ref "PHASE_A") (pin "4") (pinfunction "4_4") (pintype "passive"))
      (node (ref "R23") (pin "1") (pinfunction "1_1") (pintype "passive"))
    )
    (net (code "47") (name "/PHASE_B") (class "Default")
      (node (ref "*2 UCC27211D") (pin "4") (pinfunction "HS_4") (pintype "passive"))
      (node (ref "C27") (pin "2") (pinfunction "2_2") (pintype "passive"))
      (node (ref "PHASE_B") (pin "4") (pinfunction "4_4") (pintype "passive"))
      (node (ref "R18") (pin "1") (pinfunction "1_1") (pintype "passive"))
    )
    (net (code "48") (name "/PHASE_C") (class "Default")
      (node (ref "*3 UCC27211D") (pin "4") (pinfunction "HS_4") (pintype "passive"))
      (node (ref "C22") (pin "2") (pinfunction "2_2") (pintype "passive"))
      (node (ref "PHASE_C") (pin "4") (pinfunction "4_4") (pintype "passive"))
      (node (ref "R13") (pin "1") (pinfunction "1_1") (pintype "passive"))
    )
    (net (code "49") (name "/PWM_OUT") (class "Default")
      (node (ref "IC201") (pin "40") (pinfunction "PC9_40") (pintype "passive"))
    )
    (net (code "50") (name "/PWM_ext") (class "Default")
      (node (ref "IC201") (pin "14") (pinfunction "PA0-WKUP_14") (pintype "passive"))
      (node (ref "Q4") (pin "3") (pinfunction "C_3") (pintype "passive"))
      (node (ref "R28") (pin "2") (pinfunction "2_2") (pintype "passive"))
    )
    (net (code "51") (name "/Q0") (class "Default")
      (node (ref "C13") (pin "2") (pinfunction "2_2") (pintype "passive"))
      (node (ref "IC201") (pin "6") (pinfunction "PD1_6") (pintype "passive"))
      (node (ref "XT1") (pin "1") (pintype "passive"))
    )
    (net (code "52") (name "/SENSE_A") (class "Default")
      (node (ref "C32") (pin "1") (pinfunction "1_1") (pintype "passive"))
      (node (ref "IC201") (pin "15") (pinfunction "PA1_15") (pintype "passive"))
      (node (ref "R23") (pin "2") (pinfunction "2_2") (pintype "passive"))
      (node (ref "R24") (pin "2") (pinfunction "2_2") (pintype "passive"))
    )
    (net (code "53") (name "/SENSE_B") (class "Default")
      (node (ref "C28") (pin "1") (pinfunction "1_1") (pintype "passive"))
      (node (ref "IC201") (pin "16") (pinfunction "PA2_16") (pintype "passive"))
      (node (ref "R18") (pin "2") (pinfunction "2_2") (pintype "passive"))
      (node (ref "R20") (pin "2") (pinfunction "2_2") (pintype "passive"))
    )
    (net (code "54") (name "/SENSE_C") (class "Default")
      (node (ref "C23") (pin "1") (pinfunction "1_1") (pintype "passive"))
      (node (ref "IC201") (pin "17") (pinfunction "PA3_17") (pintype "passive"))
      (node (ref "R13") (pin "2") (pinfunction "2_2") (pintype "passive"))
      (node (ref "R15") (pin "2") (pinfunction "2_2") (pintype "passive"))
    )
    (net (code "55") (name "/SENSE_CURRENT") (class "Default")
      (node (ref "IC201") (pin "21") (pinfunction "PA5_21") (pintype "passive"))
    )
    (net (code "56") (name "/SENSE_VIN") (class "Default")
      (node (ref "IC201") (pin "20") (pinfunction "PA4_20") (pintype "passive"))
    )
    (net (code "57") (name "/SWCLK") (class "Default")
      (node (ref "IC201") (pin "49") (pinfunction "PA14_49") (pintype "passive"))
      (node (ref "PROG") (pin "5") (pinfunction "5_5") (pintype "passive"))
    )
    (net (code "58") (name "/SWDIO") (class "Default")
      (node (ref "IC201") (pin "46") (pinfunction "PA13_46") (pintype "passive"))
      (node (ref "PROG") (pin "4") (pinfunction "4_4") (pintype "passive"))
    )
    (net (code "59") (name "/TSENS_OS") (class "Default")
      (node (ref "IC201") (pin "56") (pinfunction "PB4_56") (pintype "passive"))
      (node (ref "IC203") (pin "3") (pinfunction "OS_3") (pintype "passive"))
    )
    (net (code "60") (name "/USART1_RX") (class "Default")
      (node (ref "IC201") (pin "59") (pinfunction "PB7_59") (pintype "passive"))
      (node (ref "R201") (pin "2") (pinfunction "2_2") (pintype "passive"))
    )
    (net (code "61") (name "/USART1_TX") (class "Default")
      (node (ref "IC201") (pin "58") (pinfunction "PB6_58") (pintype "passive"))
      (node (ref "R200") (pin "2") (pinfunction "2_2") (pintype "passive"))
    )
    (net (code "62") (name "/V_SENSE") (class "Default")
      (node (ref "C18") (pin "2") (pinfunction "2_2") (pintype "passive"))
      (node (ref "IC201") (pin "25") (pinfunction "PC5_25") (pintype "passive"))
      (node (ref "R10") (pin "1") (pinfunction "1_1") (pintype "passive"))
      (node (ref "R9") (pin "2") (pinfunction "2_2") (pintype "passive"))
    )
    (net (code "63") (name "12V") (class "Default")
      (node (ref "C14") (pin "2") (pinfunction "2_2") (pintype "passive"))
      (node (ref "C15") (pin "2") (pinfunction "2_2") (pintype "passive"))
      (node (ref "C3") (pin "2") (pinfunction "2_2") (pintype "passive"))
      (node (ref "FAN_12V") (pin "2") (pinfunction "2_2") (pintype "passive"))
      (node (ref "L1") (pin "2") (pinfunction "2_2") (pintype "passive"))
      (node (ref "L2") (pin "2") (pinfunction "2_2") (pintype "passive"))
      (node (ref "L4") (pin "2") (pinfunction "2_2") (pintype "passive"))
      (node (ref "L6") (pin "2") (pinfunction "2_2") (pintype "passive"))
      (node (ref "LDO_3.3V") (pin "3") (pinfunction "IN_3") (pintype "power_in"))
      (node (ref "LDO_5V") (pin "3") (pinfunction "IN_3") (pintype "power_in"))
      (node (ref "R4") (pin "2") (pinfunction "2_2") (pintype "passive"))
    )
    (net (code "64") (name "GND") (class "Default")
      (node (ref "*6") (pin "5") (pinfunction "GND_5") (pintype "passive"))
      (node (ref "1_CAN_transiver") (pin "2") (pinfunction "GND_2") (pintype "passive"))
      (node (ref "1_CURRENT_SENCE") (pin "2") (pinfunction "2_2") (pintype "passive"))
      (node (ref "1_I2C") (pin "4") (pinfunction "4_4") (pintype "passive"))
      (node (ref "1_I2C") (pin "M$0_M$1") (pinfunction "GND_M$0_M$1") (pintype "passive"))
      (node (ref "1_UAVCAN") (pin "4") (pinfunction "4_4") (pintype "passive"))
      (node (ref "1_UAVCAN") (pin "M$0_M$1") (pinfunction "GND_M$0_M$1") (pintype "passive"))
      (node (ref "2_CAN_transiver") (pin "2") (pinfunction "GND_2") (pintype "passive"))
      (node (ref "2_UAVCAN") (pin "4") (pinfunction "4_4") (pintype "passive"))
      (node (ref "2_UAVCAN") (pin "M$0_M$1") (pinfunction "GND_M$0_M$1") (pintype "passive"))
      (node (ref "3_UAVCAN") (pin "4") (pinfunction "4_4") (pintype "passive"))
      (node (ref "3_UAVCAN") (pin "M$0_M$1") (pinfunction "GND_M$0_M$1") (pintype "passive"))
      (node (ref "4_UAVCAN") (pin "4") (pinfunction "4_4") (pintype "passive"))
      (node (ref "4_UAVCAN") (pin "M$0_M$1") (pinfunction "GND_M$0_M$1") (pintype "passive"))
      (node (ref "C10") (pin "1") (pinfunction "1_1") (pintype "passive"))
      (node (ref "C11") (pin "1") (pinfunction "1_1") (pintype "passive"))
      (node (ref "C12") (pin "1") (pinfunction "1_1") (pintype "passive"))
      (node (ref "C13") (pin "1") (pinfunction "1_1") (pintype "passive"))
      (node (ref "C14") (pin "1") (pinfunction "1_1") (pintype "passive"))
      (node (ref "C15") (pin "1") (pinfunction "1_1") (pintype "passive"))
      (node (ref "C16") (pin "1") (pinfunction "1_1") (pintype "passive"))
      (node (ref "C17") (pin "1") (pinfunction "1_1") (pintype "passive"))
      (node (ref "C18") (pin "1") (pinfunction "1_1") (pintype "passive"))
      (node (ref "C19") (pin "2") (pinfunction "2_2") (pintype "passive"))
      (node (ref "C2") (pin "1") (pinfunction "1_1") (pintype "passive"))
      (node (ref "C20") (pin "1") (pinfunction "1_1") (pintype "passive"))
      (node (ref "C23") (pin "2") (pinfunction "2_2") (pintype "passive"))
      (node (ref "C24") (pin "2") (pinfunction "2_2") (pintype "passive"))
      (node (ref "C26") (pin "1") (pinfunction "1_1") (pintype "passive"))
      (node (ref "C28") (pin "2") (pinfunction "2_2") (pintype "passive"))
      (node (ref "C29") (pin "2") (pinfunction "2_2") (pintype "passive"))
      (node (ref "C3") (pin "1") (pinfunction "1_1") (pintype "passive"))
      (node (ref "C32") (pin "2") (pinfunction "2_2") (pintype "passive"))
      (node (ref "C34") (pin "1") (pinfunction "1_1") (pintype "passive"))
      (node (ref "C4") (pin "1") (pinfunction "1_1") (pintype "passive"))
      (node (ref "C5") (pin "1") (pinfunction "1_1") (pintype "passive"))
      (node (ref "C6") (pin "2") (pinfunction "2_2") (pintype "passive"))
      (node (ref "C7") (pin "2") (pinfunction "2_2") (pintype "passive"))
      (node (ref "C8") (pin "1") (pinfunction "1_1") (pintype "passive"))
      (node (ref "C9") (pin "1") (pinfunction "1_1") (pintype "passive"))
      (node (ref "D1") (pin "1") (pinfunction "2_1") (pintype "passive"))
      (node (ref "D2") (pin "2") (pinfunction "A_2") (pintype "passive"))
      (node (ref "D3") (pin "2") (pinfunction "A_2") (pintype "passive"))
      (node (ref "D4") (pin "2") (pinfunction "A_2") (pintype "passive"))
      (node (ref "ENCODER") (pin "1") (pinfunction "1_1") (pintype "passive"))
      (node (ref "FAN_12V") (pin "1") (pinfunction "1_1") (pintype "passive"))
      (node (ref "IC201") (pin "10") (pinfunction "PC2_10") (pintype "passive"))
      (node (ref "IC201") (pin "11") (pinfunction "PC3_11") (pintype "passive"))
      (node (ref "IC201") (pin "12") (pinfunction "VSSA_12") (pintype "passive"))
      (node (ref "IC201") (pin "18") (pinfunction "VSS_18") (pintype "passive"))
      (node (ref "IC201") (pin "31") (pinfunction "VSS_31") (pintype "passive"))
      (node (ref "IC201") (pin "47") (pinfunction "VSS_47") (pintype "passive"))
      (node (ref "IC201") (pin "63") (pinfunction "VSS_63") (pintype "passive"))
      (node (ref "IC201") (pin "9") (pinfunction "PC1_9") (pintype "passive"))
      (node (ref "IC203") (pin "4") (pinfunction "GND_4") (pintype "passive"))
      (node (ref "IC203") (pin "5") (pinfunction "A2_5") (pintype "passive"))
      (node (ref "IC203") (pin "6") (pinfunction "A1_6") (pintype "passive"))
      (node (ref "IC203") (pin "7") (pinfunction "A0_7") (pintype "passive"))
      (node (ref "L3") (pin "1") (pinfunction "1_1") (pintype "passive"))
      (node (ref "L5") (pin "1") (pinfunction "1_1") (pintype "passive"))
      (node (ref "L7") (pin "1") (pinfunction "1_1") (pintype "passive"))
      (node (ref "LDO_3.3V") (pin "1") (pinfunction "GND_1") (pintype "power_in"))
      (node (ref "LDO_5V") (pin "1") (pinfunction "GND_1") (pintype "power_in"))
      (node (ref "P1") (pin "1") (pinfunction "1_1") (pintype "passive"))
      (node (ref "PROG") (pin "6") (pinfunction "6_6") (pintype "passive"))
      (node (ref "PROG") (pin "M") (pinfunction "M_M") (pintype "passive"))
      (node (ref "Q4") (pin "2") (pinfunction "E_2") (pintype "passive"))
      (node (ref "R10") (pin "2") (pinfunction "2_2") (pintype "passive"))
      (node (ref "R15") (pin "1") (pinfunction "1_1") (pintype "passive"))
      (node (ref "R20") (pin "1") (pinfunction "1_1") (pintype "passive"))
      (node (ref "R204") (pin "1") (pinfunction "1_1") (pintype "passive"))
      (node (ref "R24") (pin "1") (pinfunction "1_1") (pintype "passive"))
      (node (ref "R26") (pin "2") (pinfunction "2_2") (pintype "passive"))
      (node (ref "R5") (pin "2") (pinfunction "2_2") (pintype "passive"))
      (node (ref "R6") (pin "1") (pinfunction "1_1") (pintype "passive"))
      (node (ref "R7") (pin "1") (pinfunction "1_1") (pintype "passive"))
      (node (ref "R8") (pin "1") (pinfunction "1_1") (pintype "passive"))
      (node (ref "TERMO_FUSE") (pin "1") (pinfunction "1_1") (pintype "passive"))
      (node (ref "TPS_54360") (pin "7") (pinfunction "GND_7") (pintype "power_in"))
      (node (ref "TPS_54360") (pin "9") (pinfunction "PDN_9") (pintype "power_in"))
      (node (ref "XT1") (pin "G") (pintype "passive"))
    )
    (net (code "65") (name "Net-(*1 UCC27211D-HB)") (class "Default")
      (node (ref "*1 UCC27211D") (pin "2") (pinfunction "HB_2") (pintype "passive"))
      (node (ref "C31") (pin "1") (pinfunction "1_1") (pintype "passive"))
    )
    (net (code "66") (name "Net-(*1 UCC27211D-HI)") (class "Default")
      (node (ref "*1 UCC27211D") (pin "5") (pinfunction "HI_5") (pintype "passive"))
      (node (ref "Q3") (pin "3") (pinfunction "C_3") (pintype "passive"))
      (node (ref "R21") (pin "1") (pinfunction "1_1") (pintype "passive"))
    )
    (net (code "67") (name "Net-(*1 UCC27211D-LI)") (class "Default")
      (node (ref "*1 UCC27211D") (pin "6") (pinfunction "LI_6") (pintype "passive"))
      (node (ref "R22") (pin "1") (pinfunction "1_1") (pintype "passive"))
    )
    (net (code "68") (name "Net-(*1 UCC27211D-VDD)") (class "Default")
      (node (ref "*1 UCC27211D") (pin "1") (pinfunction "VDD_1") (pintype "passive"))
      (node (ref "C30") (pin "1") (pinfunction "1_1") (pintype "passive"))
      (node (ref "L6") (pin "1") (pinfunction "1_1") (pintype "passive"))
    )
    (net (code "69") (name "Net-(*2 UCC27211D-HB)") (class "Default")
      (node (ref "*2 UCC27211D") (pin "2") (pinfunction "HB_2") (pintype "passive"))
      (node (ref "C27") (pin "1") (pinfunction "1_1") (pintype "passive"))
    )
    (net (code "70") (name "Net-(*2 UCC27211D-HI)") (class "Default")
      (node (ref "*2 UCC27211D") (pin "5") (pinfunction "HI_5") (pintype "passive"))
      (node (ref "Q2") (pin "3") (pinfunction "C_3") (pintype "passive"))
      (node (ref "R16") (pin "1") (pinfunction "1_1") (pintype "passive"))
    )
    (net (code "71") (name "Net-(*2 UCC27211D-LI)") (class "Default")
      (node (ref "*2 UCC27211D") (pin "6") (pinfunction "LI_6") (pintype "passive"))
      (node (ref "R17") (pin "1") (pinfunction "1_1") (pintype "passive"))
    )
    (net (code "72") (name "Net-(*2 UCC27211D-VDD)") (class "Default")
      (node (ref "*2 UCC27211D") (pin "1") (pinfunction "VDD_1") (pintype "passive"))
      (node (ref "C25") (pin "1") (pinfunction "1_1") (pintype "passive"))
      (node (ref "L4") (pin "1") (pinfunction "1_1") (pintype "passive"))
    )
    (net (code "73") (name "Net-(*3 UCC27211D-HB)") (class "Default")
      (node (ref "*3 UCC27211D") (pin "2") (pinfunction "HB_2") (pintype "passive"))
      (node (ref "C22") (pin "1") (pinfunction "1_1") (pintype "passive"))
    )
    (net (code "74") (name "Net-(*3 UCC27211D-HI)") (class "Default")
      (node (ref "*3 UCC27211D") (pin "5") (pinfunction "HI_5") (pintype "passive"))
      (node (ref "Q1") (pin "3") (pinfunction "C_3") (pintype "passive"))
      (node (ref "R11") (pin "1") (pinfunction "1_1") (pintype "passive"))
    )
    (net (code "75") (name "Net-(*3 UCC27211D-LI)") (class "Default")
      (node (ref "*3 UCC27211D") (pin "6") (pinfunction "LI_6") (pintype "passive"))
      (node (ref "R12") (pin "1") (pinfunction "1_1") (pintype "passive"))
    )
    (net (code "76") (name "Net-(*3 UCC27211D-VDD)") (class "Default")
      (node (ref "*3 UCC27211D") (pin "1") (pinfunction "VDD_1") (pintype "passive"))
      (node (ref "C21") (pin "1") (pinfunction "1_1") (pintype "passive"))
      (node (ref "L2") (pin "1") (pinfunction "1_1") (pintype "passive"))
    )
    (net (code "77") (name "Net-(*6-Anode(+))") (class "Default")
      (node (ref "*6") (pin "2") (pinfunction "Anode(+)_2") (pintype "passive"))
      (node (ref "C33") (pin "2") (pinfunction "2_2") (pintype "passive"))
      (node (ref "R31") (pin "2") (pinfunction "2_2") (pintype "passive"))
    )
    (net (code "78") (name "Net-(*6-Kathode(-))") (class "Default")
      (node (ref "*6") (pin "3") (pinfunction "Kathode(-)_3") (pintype "passive"))
      (node (ref "C33") (pin "1") (pinfunction "1_1") (pintype "passive"))
      (node (ref "PWM") (pin "1") (pinfunction "1_1") (pintype "passive"))
    )
    (net (code "79") (name "Net-(*6-Ven)") (class "Default")
      (node (ref "*6") (pin "7") (pinfunction "Ven_7") (pintype "passive"))
      (node (ref "R29") (pin "2") (pinfunction "2_2") (pintype "passive"))
    )
    (net (code "80") (name "Net-(*6-Vout)") (class "Default")
      (node (ref "*6") (pin "6") (pinfunction "Vout_6") (pintype "passive"))
      (node (ref "Q4") (pin "1") (pinfunction "B_1") (pintype "passive"))
      (node (ref "R30") (pin "2") (pinfunction "2_2") (pintype "passive"))
    )
    (net (code "81") (name "Net-(1_CAN_transiver-CANH)") (class "Default")
      (node (ref "1_CAN_transiver") (pin "7") (pinfunction "CANH_7") (pintype "passive"))
      (node (ref "1_UAVCAN") (pin "2") (pinfunction "2_2") (pintype "passive"))
      (node (ref "2_UAVCAN") (pin "2") (pinfunction "2_2") (pintype "passive"))
    )
    (net (code "82") (name "Net-(1_CAN_transiver-CANL)") (class "Default")
      (node (ref "1_CAN_transiver") (pin "6") (pinfunction "CANL_6") (pintype "passive"))
      (node (ref "1_UAVCAN") (pin "3") (pinfunction "3_3") (pintype "passive"))
      (node (ref "2_UAVCAN") (pin "3") (pinfunction "3_3") (pintype "passive"))
    )
    (net (code "83") (name "Net-(1_CURRENT_SENCE-Pad1)") (class "Default")
      (node (ref "1_CURRENT_SENCE") (pin "1") (pinfunction "1_1") (pintype "passive"))
      (node (ref "R27") (pin "1") (pinfunction "1_1") (pintype "passive"))
    )
    (net (code "84") (name "Net-(1_UAVCAN-Pad1)") (class "Default")
      (node (ref "1_UAVCAN") (pin "1") (pinfunction "1_1") (pintype "passive"))
      (node (ref "2_UAVCAN") (pin "1") (pinfunction "1_1") (pintype "passive"))
    )
    (net (code "85") (name "Net-(2_CAN_transiver-CANH)") (class "Default")
      (node (ref "2_CAN_transiver") (pin "7") (pinfunction "CANH_7") (pintype "passive"))
      (node (ref "3_UAVCAN") (pin "2") (pinfunction "2_2") (pintype "passive"))
      (node (ref "4_UAVCAN") (pin "2") (pinfunction "2_2") (pintype "passive"))
    )
    (net (code "86") (name "Net-(2_CAN_transiver-CANL)") (class "Default")
      (node (ref "2_CAN_transiver") (pin "6") (pinfunction "CANL_6") (pintype "passive"))
      (node (ref "3_UAVCAN") (pin "3") (pinfunction "3_3") (pintype "passive"))
      (node (ref "4_UAVCAN") (pin "3") (pinfunction "3_3") (pintype "passive"))
    )
    (net (code "87") (name "Net-(3_UAVCAN-Pad1)") (class "Default")
      (node (ref "3_UAVCAN") (pin "1") (pinfunction "1_1") (pintype "passive"))
      (node (ref "4_UAVCAN") (pin "1") (pinfunction "1_1") (pintype "passive"))
    )
    (net (code "88") (name "Net-(C7-Pad1)") (class "Default")
      (node (ref "C7") (pin "1") (pinfunction "1_1") (pintype "passive"))
      (node (ref "R3") (pin "1") (pinfunction "1_1") (pintype "passive"))
    )
    (net (code "89") (name "Net-(PROG-Pad2)") (class "Default")
      (node (ref "PROG") (pin "2") (pinfunction "2_2") (pintype "passive"))
      (node (ref "R200") (pin "1") (pinfunction "1_1") (pintype "passive"))
    )
    (net (code "90") (name "Net-(PROG-Pad3)") (class "Default")
      (node (ref "PROG") (pin "3") (pinfunction "3_3") (pintype "passive"))
      (node (ref "R201") (pin "1") (pinfunction "1_1") (pintype "passive"))
    )
    (net (code "91") (name "Net-(PWM-Pad3)") (class "Default")
      (node (ref "PWM") (pin "3") (pinfunction "3_3") (pintype "passive"))
      (node (ref "R31") (pin "1") (pinfunction "1_1") (pintype "passive"))
    )
    (net (code "92") (name "Net-(Q1-B)") (class "Default")
      (node (ref "Q1") (pin "1") (pinfunction "B_1") (pintype "passive"))
      (node (ref "R14") (pin "1") (pinfunction "1_1") (pintype "passive"))
    )
    (net (code "93") (name "Net-(Q2-B)") (class "Default")
      (node (ref "Q2") (pin "1") (pinfunction "B_1") (pintype "passive"))
      (node (ref "R19") (pin "1") (pinfunction "1_1") (pintype "passive"))
    )
    (net (code "94") (name "Net-(Q3-B)") (class "Default")
      (node (ref "Q3") (pin "1") (pinfunction "B_1") (pintype "passive"))
      (node (ref "R25") (pin "1") (pinfunction "1_1") (pintype "passive"))
    )
    (net (code "95") (name "Net-(TPS_54360-BOOT)") (class "Default")
      (node (ref "C1") (pin "1") (pinfunction "1_1") (pintype "passive"))
      (node (ref "TPS_54360") (pin "1") (pinfunction "BOOT_1") (pintype "power_in"))
    )
    (net (code "96") (name "Net-(TPS_54360-COMP)") (class "Default")
      (node (ref "C6") (pin "1") (pinfunction "1_1") (pintype "passive"))
      (node (ref "R3") (pin "2") (pinfunction "2_2") (pintype "passive"))
      (node (ref "TPS_54360") (pin "6") (pinfunction "COMP_6") (pintype "passive"))
    )
    (net (code "97") (name "Net-(TPS_54360-FB)") (class "Default")
      (node (ref "R4") (pin "1") (pinfunction "1_1") (pintype "passive"))
      (node (ref "R6") (pin "2") (pinfunction "2_2") (pintype "passive"))
      (node (ref "TPS_54360") (pin "5") (pinfunction "FB_5") (pintype "power_in"))
    )
    (net (code "98") (name "Net-(TPS_54360-ON{slash}~{OFF})") (class "Default")
      (node (ref "R2") (pin "1") (pinfunction "1_1") (pintype "passive"))
      (node (ref "R7") (pin "2") (pinfunction "2_2") (pintype "passive"))
      (node (ref "TPS_54360") (pin "3") (pinfunction "ON/~{OFF}_3") (pintype "input"))
    )
    (net (code "99") (name "Net-(TPS_54360-RT{slash}CLK)") (class "Default")
      (node (ref "R5") (pin "1") (pinfunction "1_1") (pintype "passive"))
      (node (ref "TPS_54360") (pin "4") (pinfunction "RT/CLK_4") (pintype "passive"))
    )
    (net (code "100") (name "Net-(TPS_54360-SW)") (class "Default")
      (node (ref "C1") (pin "2") (pinfunction "2_2") (pintype "passive"))
      (node (ref "D1") (pin "2") (pinfunction "2_2") (pintype "passive"))
      (node (ref "L1") (pin "1") (pinfunction "1_1") (pintype "passive"))
      (node (ref "TPS_54360") (pin "8") (pinfunction "SW_8") (pintype "power_in"))
    )
    (net (code "101") (name "Net-(TPS_54360-VIN)") (class "Default")
      (node (ref "C4") (pin "2") (pinfunction "2_2") (pintype "passive"))
      (node (ref "R1") (pin "1") (pinfunction "1_1") (pintype "passive"))
      (node (ref "R2") (pin "2") (pinfunction "2_2") (pintype "passive"))
      (node (ref "TPS_54360") (pin "2") (pinfunction "VIN_2") (pintype "input"))
    )
    (net (code "102") (name "VCC_3.3") (class "Default")
      (node (ref "1_CAN_transiver") (pin "3") (pinfunction "VCC_3") (pintype "passive"))
      (node (ref "2_CAN_transiver") (pin "3") (pinfunction "VCC_3") (pintype "passive"))
      (node (ref "C10") (pin "2") (pinfunction "2_2") (pintype "passive"))
      (node (ref "C11") (pin "2") (pinfunction "2_2") (pintype "passive"))
      (node (ref "C17") (pin "2") (pinfunction "2_2") (pintype "passive"))
      (node (ref "C19") (pin "1") (pinfunction "1_1") (pintype "passive"))
      (node (ref "C2") (pin "2") (pinfunction "2_2") (pintype "passive"))
      (node (ref "C24") (pin "1") (pinfunction "1_1") (pintype "passive"))
      (node (ref "C26") (pin "2") (pinfunction "2_2") (pintype "passive"))
      (node (ref "C29") (pin "1") (pinfunction "1_1") (pintype "passive"))
      (node (ref "C5") (pin "2") (pinfunction "2_2") (pintype "passive"))
      (node (ref "C8") (pin "2") (pinfunction "2_2") (pintype "passive"))
      (node (ref "C9") (pin "2") (pinfunction "2_2") (pintype "passive"))
      (node (ref "IC201") (pin "1") (pinfunction "VBAT_1") (pintype "passive"))
      (node (ref "IC201") (pin "13") (pinfunction "VDDA_13") (pintype "passive"))
      (node (ref "IC201") (pin "19") (pinfunction "VDD_19") (pintype "passive"))
      (node (ref "IC201") (pin "32") (pinfunction "VDD_32") (pintype "passive"))
      (node (ref "IC201") (pin "48") (pinfunction "VDD_48") (pintype "passive"))
      (node (ref "IC201") (pin "64") (pinfunction "VDD_64") (pintype "passive"))
      (node (ref "IC203") (pin "8") (pinfunction "VCC_8") (pintype "passive"))
      (node (ref "LDO_3.3V") (pin "2") (pinfunction "OUT_2") (pintype "power_in"))
      (node (ref "LDO_3.3V") (pin "4") (pinfunction "OUT_4") (pintype "power_in"))
      (node (ref "PROG") (pin "1") (pinfunction "1_1") (pintype "passive"))
      (node (ref "R202") (pin "1") (pinfunction "1_1") (pintype "passive"))
      (node (ref "R203") (pin "1") (pinfunction "1_1") (pintype "passive"))
      (node (ref "R205") (pin "2") (pinfunction "2_2") (pintype "passive"))
      (node (ref "R28") (pin "1") (pinfunction "1_1") (pintype "passive"))
      (node (ref "R30") (pin "1") (pinfunction "1_1") (pintype "passive"))
    )
    (net (code "103") (name "VCC_5") (class "Default")
      (node (ref "*6") (pin "8") (pinfunction "VCC_8") (pintype "passive"))
      (node (ref "1_CURRENT_SENCE") (pin "3") (pinfunction "3_3") (pintype "passive"))
      (node (ref "1_I2C") (pin "1") (pinfunction "1_1") (pintype "passive"))
      (node (ref "C16") (pin "2") (pinfunction "2_2") (pintype "passive"))
      (node (ref "C20") (pin "2") (pinfunction "2_2") (pintype "passive"))
      (node (ref "C34") (pin "2") (pinfunction "2_2") (pintype "passive"))
      (node (ref "ENCODER") (pin "2") (pinfunction "2_2") (pintype "passive"))
      (node (ref "LDO_5V") (pin "2") (pinfunction "OUT_2") (pintype "power_in"))
      (node (ref "LDO_5V") (pin "4") (pinfunction "OUT_4") (pintype "power_in"))
      (node (ref "R29") (pin "1") (pinfunction "1_1") (pintype "passive"))
    )
    (net (code "104") (name "VCC_50v") (class "Default")
      (node (ref "P1") (pin "2") (pinfunction "2_2") (pintype "passive"))
      (node (ref "R1") (pin "2") (pinfunction "2_2") (pintype "passive"))
      (node (ref "R9") (pin "1") (pinfunction "1_1") (pintype "passive"))
    )
    (net (code "105") (name "unconnected-(*6-N{slash}C-Pad1)") (class "Default")
      (node (ref "*6") (pin "1") (pinfunction "N/C_1") (pintype "passive"))
    )
    (net (code "106") (name "unconnected-(*6-N{slash}C-Pad4)") (class "Default")
      (node (ref "*6") (pin "4") (pinfunction "N/C_4") (pintype "passive"))
    )
    (net (code "107") (name "unconnected-(1_CAN_transiver-NC-Pad5)") (class "Default")
      (node (ref "1_CAN_transiver") (pin "5") (pinfunction "NC_5") (pintype "passive"))
    )
    (net (code "108") (name "unconnected-(1_CAN_transiver-NC-Pad8)") (class "Default")
      (node (ref "1_CAN_transiver") (pin "8") (pinfunction "NC_8") (pintype "passive"))
    )
    (net (code "109") (name "unconnected-(2_CAN_transiver-NC-Pad5)") (class "Default")
      (node (ref "2_CAN_transiver") (pin "5") (pinfunction "NC_5") (pintype "passive"))
    )
    (net (code "110") (name "unconnected-(2_CAN_transiver-NC-Pad8)") (class "Default")
      (node (ref "2_CAN_transiver") (pin "8") (pinfunction "NC_8") (pintype "passive"))
    )
    (net (code "111") (name "unconnected-(BQ1-Pad1)") (class "Default")
      (node (ref "BQ1") (pin "1") (pinfunction "1_1") (pintype "passive"))
    )
    (net (code "112") (name "unconnected-(BQ1-Pad2)") (class "Default")
      (node (ref "BQ1") (pin "2") (pinfunction "2_2") (pintype "passive"))
    )
    (net (code "113") (name "unconnected-(PWM-Pad2)") (class "Default")
      (node (ref "PWM") (pin "2") (pinfunction "2_2") (pintype "passive"))
    )
  )
)
